# FLEX_OUTPUT.net
KiCad netlist of a schematic drawn in Altium Designer
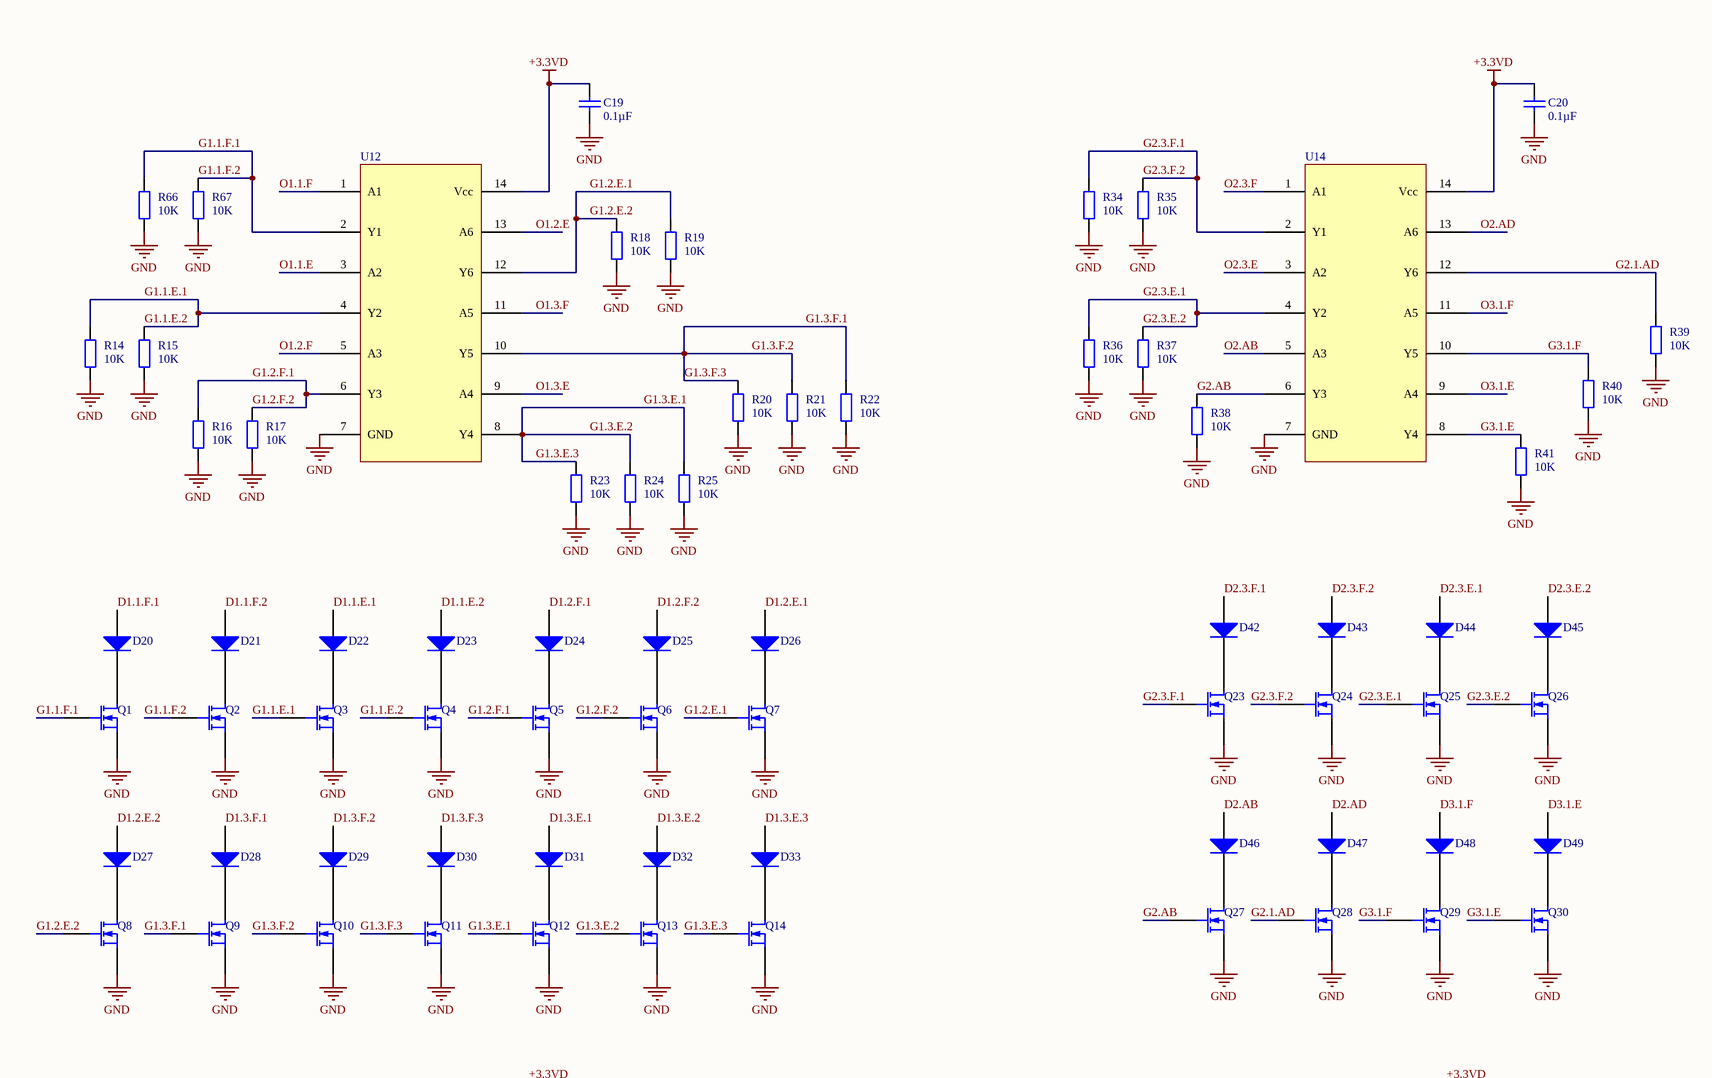
[diagram p0: FLEX_OUTPUT.SchDoc, top left]
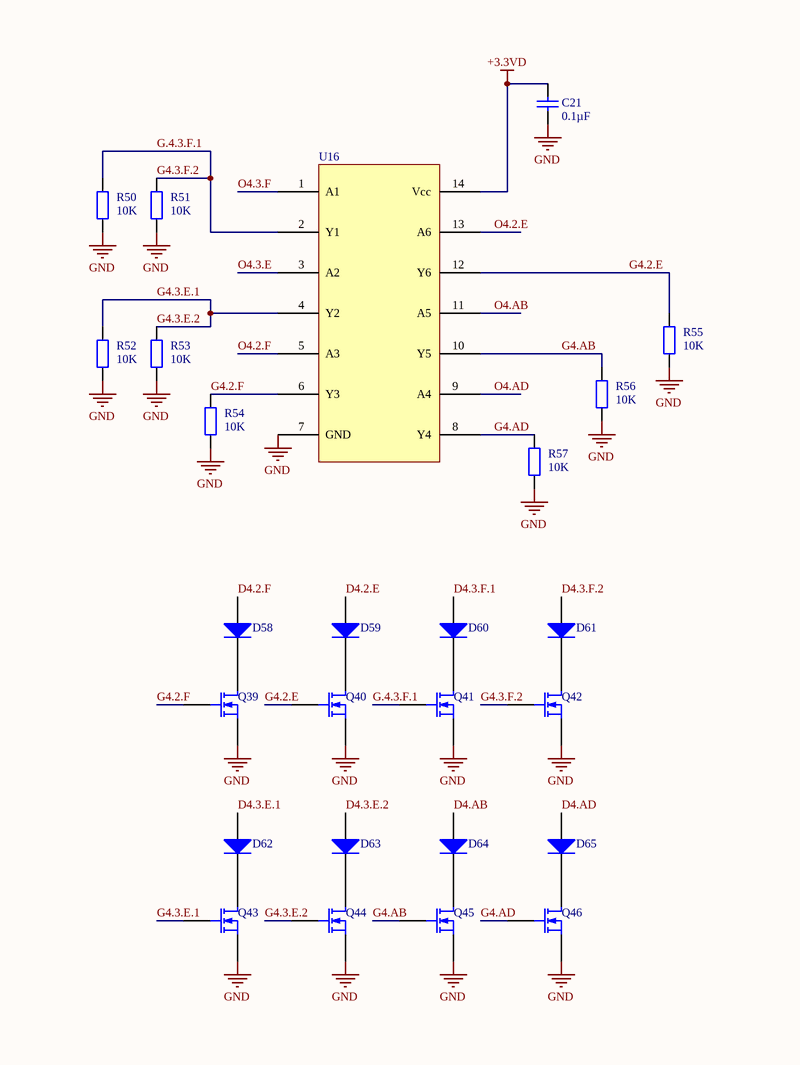
[diagram p1: FLEX_OUTPUT.SchDoc, top right]
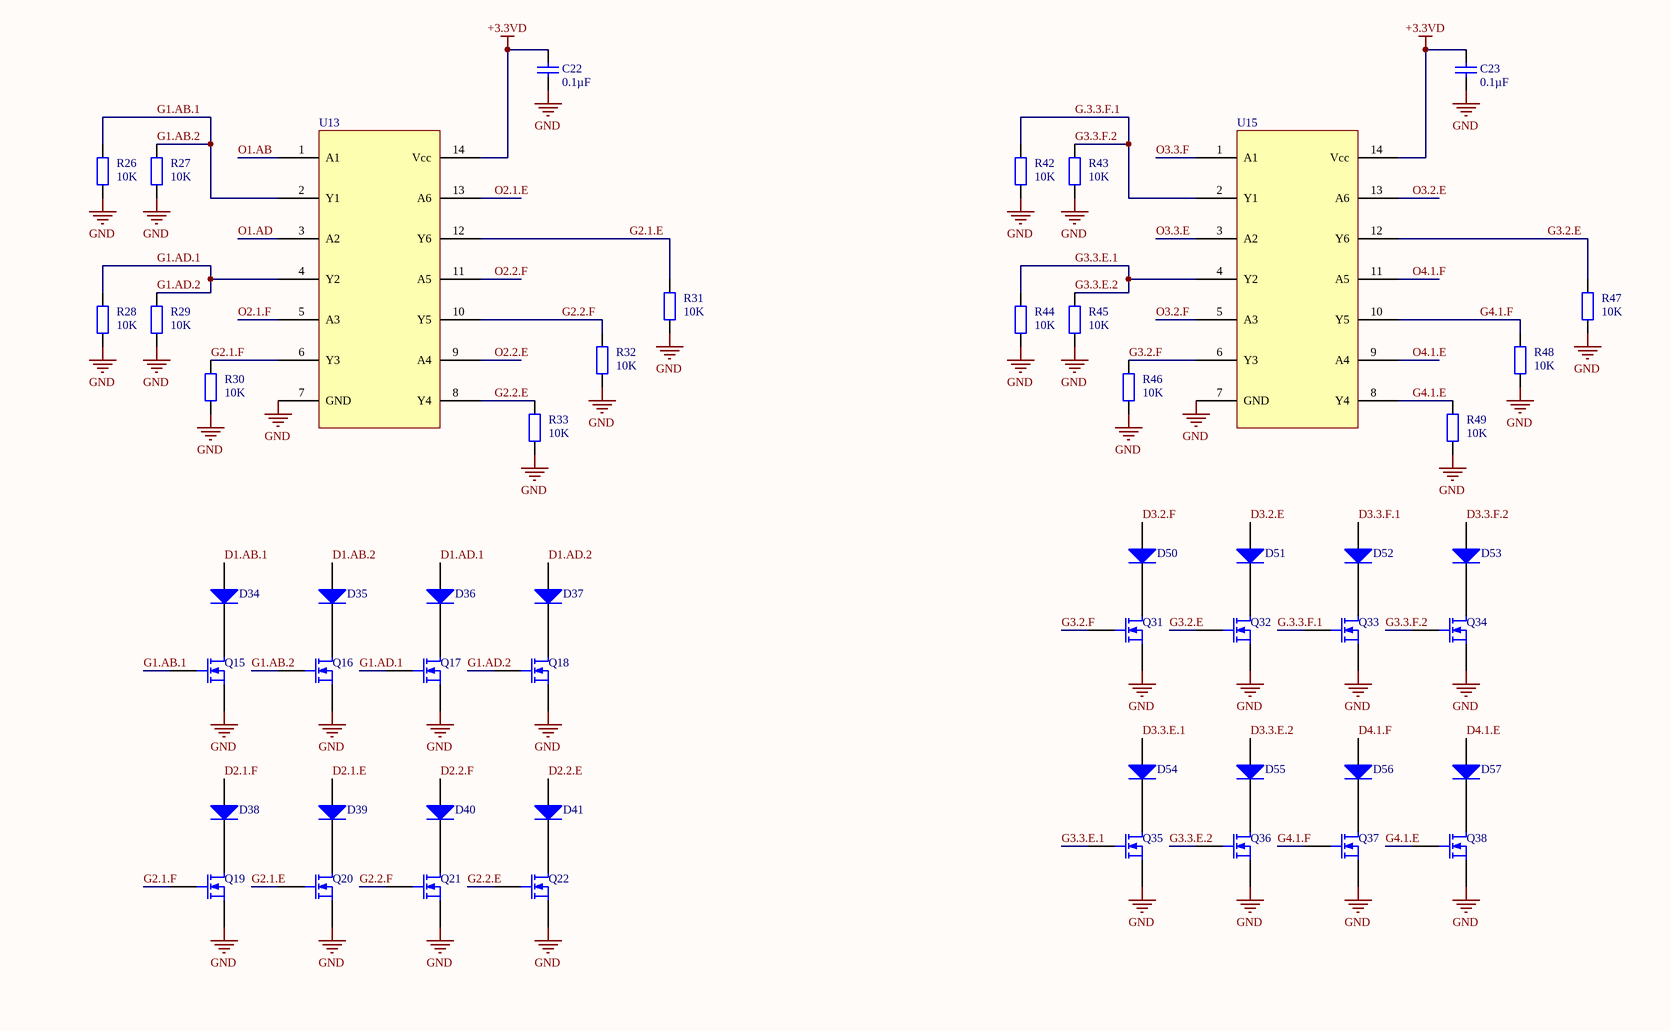
[diagram p2: FLEX_OUTPUT.SchDoc, bottom left]
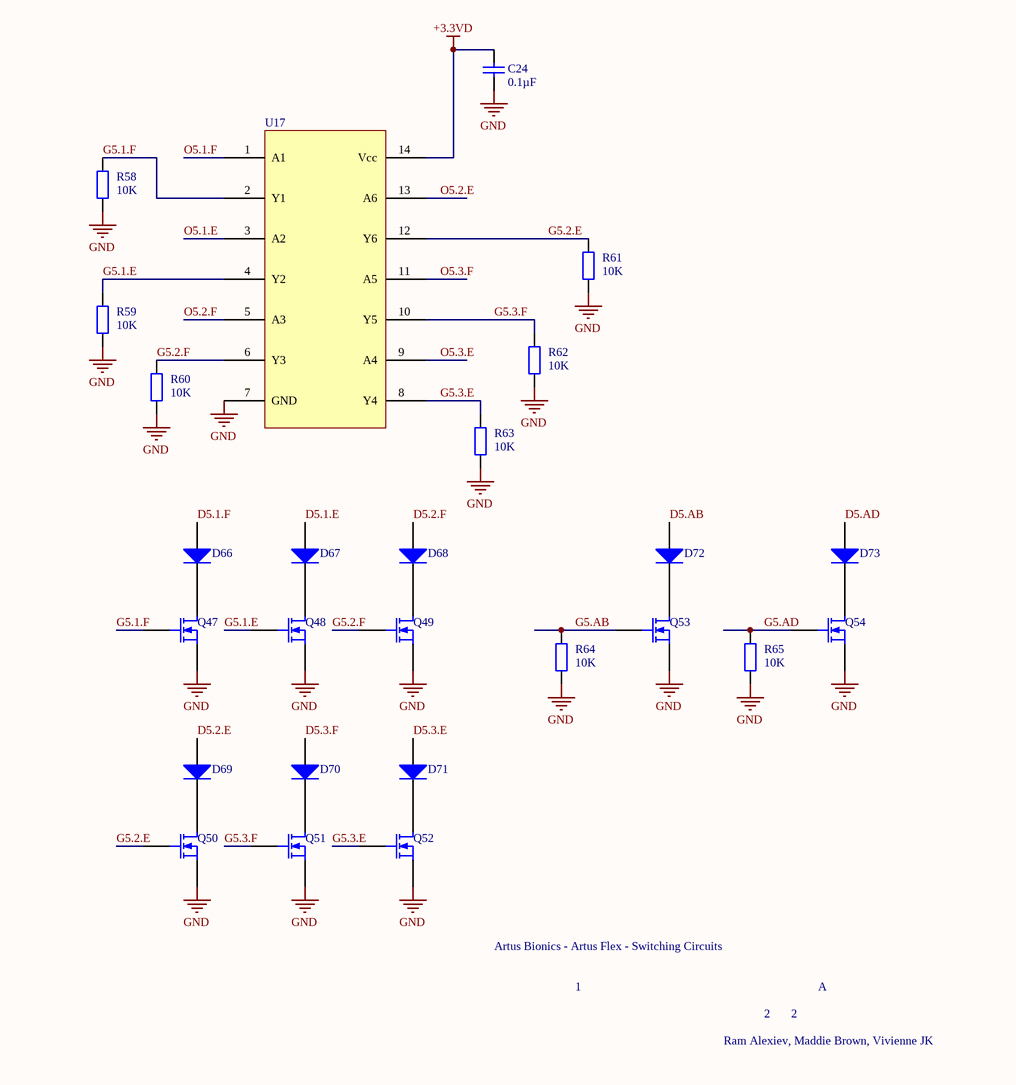
[diagram p3: FLEX_OUTPUT.SchDoc, bottom right]

(export (version "E")
  (design (tool "Eeschema 10.0.6"))
  (components
    (comp (ref "C19")
      (value "0.1µF")
      (footprint "TDK C-Series (1608)")
      (description "Capacitor")
      (fields (field (name "Comment") "Cap") (field (name "PUBLISHER") "Altium Limited"))
      (libsource (lib "Miscellaneous Devices") (part "Cap"))
    )
    (comp (ref "C20")
      (value "0.1µF")
      (footprint "TDK C-Series (1608)")
      (description "Capacitor")
      (fields (field (name "Comment") "Cap") (field (name "PUBLISHER") "Altium Limited"))
      (libsource (lib "Miscellaneous Devices") (part "Cap"))
    )
    (comp (ref "C21")
      (value "0.1µF")
      (footprint "TDK C-Series (1608)")
      (description "Capacitor")
      (fields (field (name "Comment") "Cap") (field (name "PUBLISHER") "Altium Limited"))
      (libsource (lib "Miscellaneous Devices") (part "Cap"))
    )
    (comp (ref "C22")
      (value "0.1µF")
      (footprint "TDK C-Series (1608)")
      (description "Capacitor")
      (fields (field (name "Comment") "Cap") (field (name "PUBLISHER") "Altium Limited"))
      (libsource (lib "Miscellaneous Devices") (part "Cap"))
    )
    (comp (ref "C23")
      (value "0.1µF")
      (footprint "TDK C-Series (1608)")
      (description "Capacitor")
      (fields (field (name "Comment") "Cap") (field (name "PUBLISHER") "Altium Limited"))
      (libsource (lib "Miscellaneous Devices") (part "Cap"))
    )
    (comp (ref "C24")
      (value "0.1µF")
      (footprint "TDK C-Series (1608)")
      (description "Capacitor")
      (fields (field (name "Comment") "Cap") (field (name "PUBLISHER") "Altium Limited"))
      (libsource (lib "Miscellaneous Devices") (part "Cap"))
    )
    (comp (ref "D20")
      (value "de")
      (footprint "Diode_Shottky")
      (description "Default Diode")
      (fields (field (name "PUBLISHER") "Altium Limited"))
      (libsource (lib "Miscellaneous Devices") (part "Diode"))
    )
    (comp (ref "D21")
      (value "de")
      (footprint "Diode_Shottky")
      (description "Default Diode")
      (fields (field (name "PUBLISHER") "Altium Limited"))
      (libsource (lib "Miscellaneous Devices") (part "Diode"))
    )
    (comp (ref "D22")
      (value "de")
      (footprint "Diode_Shottky")
      (description "Default Diode")
      (fields (field (name "PUBLISHER") "Altium Limited"))
      (libsource (lib "Miscellaneous Devices") (part "Diode"))
    )
    (comp (ref "D23")
      (value "de")
      (footprint "Diode_Shottky")
      (description "Default Diode")
      (fields (field (name "PUBLISHER") "Altium Limited"))
      (libsource (lib "Miscellaneous Devices") (part "Diode"))
    )
    (comp (ref "D24")
      (value "de")
      (footprint "Diode_Shottky")
      (description "Default Diode")
      (fields (field (name "PUBLISHER") "Altium Limited"))
      (libsource (lib "Miscellaneous Devices") (part "Diode"))
    )
    (comp (ref "D25")
      (value "de")
      (footprint "Diode_Shottky")
      (description "Default Diode")
      (fields (field (name "PUBLISHER") "Altium Limited"))
      (libsource (lib "Miscellaneous Devices") (part "Diode"))
    )
    (comp (ref "D26")
      (value "de")
      (footprint "Diode_Shottky")
      (description "Default Diode")
      (fields (field (name "PUBLISHER") "Altium Limited"))
      (libsource (lib "Miscellaneous Devices") (part "Diode"))
    )
    (comp (ref "D27")
      (value "de")
      (footprint "Diode_Shottky")
      (description "Default Diode")
      (fields (field (name "PUBLISHER") "Altium Limited"))
      (libsource (lib "Miscellaneous Devices") (part "Diode"))
    )
    (comp (ref "D28")
      (value "de")
      (footprint "Diode_Shottky")
      (description "Default Diode")
      (fields (field (name "PUBLISHER") "Altium Limited"))
      (libsource (lib "Miscellaneous Devices") (part "Diode"))
    )
    (comp (ref "D29")
      (value "de")
      (footprint "Diode_Shottky")
      (description "Default Diode")
      (fields (field (name "PUBLISHER") "Altium Limited"))
      (libsource (lib "Miscellaneous Devices") (part "Diode"))
    )
    (comp (ref "D30")
      (value "de")
      (footprint "Diode_Shottky")
      (description "Default Diode")
      (fields (field (name "PUBLISHER") "Altium Limited"))
      (libsource (lib "Miscellaneous Devices") (part "Diode"))
    )
    (comp (ref "D31")
      (value "de")
      (footprint "Diode_Shottky")
      (description "Default Diode")
      (fields (field (name "PUBLISHER") "Altium Limited"))
      (libsource (lib "Miscellaneous Devices") (part "Diode"))
    )
    (comp (ref "D32")
      (value "de")
      (footprint "Diode_Shottky")
      (description "Default Diode")
      (fields (field (name "PUBLISHER") "Altium Limited"))
      (libsource (lib "Miscellaneous Devices") (part "Diode"))
    )
    (comp (ref "D33")
      (value "de")
      (footprint "Diode_Shottky")
      (description "Default Diode")
      (fields (field (name "PUBLISHER") "Altium Limited"))
      (libsource (lib "Miscellaneous Devices") (part "Diode"))
    )
    (comp (ref "D34")
      (value "de")
      (footprint "Diode_Shottky")
      (description "Default Diode")
      (fields (field (name "PUBLISHER") "Altium Limited"))
      (libsource (lib "Miscellaneous Devices") (part "Diode"))
    )
    (comp (ref "D35")
      (value "de")
      (footprint "Diode_Shottky")
      (description "Default Diode")
      (fields (field (name "PUBLISHER") "Altium Limited"))
      (libsource (lib "Miscellaneous Devices") (part "Diode"))
    )
    (comp (ref "D36")
      (value "de")
      (footprint "Diode_Shottky")
      (description "Default Diode")
      (fields (field (name "PUBLISHER") "Altium Limited"))
      (libsource (lib "Miscellaneous Devices") (part "Diode"))
    )
    (comp (ref "D37")
      (value "de")
      (footprint "Diode_Shottky")
      (description "Default Diode")
      (fields (field (name "PUBLISHER") "Altium Limited"))
      (libsource (lib "Miscellaneous Devices") (part "Diode"))
    )
    (comp (ref "D38")
      (value "de")
      (footprint "Diode_Shottky")
      (description "Default Diode")
      (fields (field (name "PUBLISHER") "Altium Limited"))
      (libsource (lib "Miscellaneous Devices") (part "Diode"))
    )
    (comp (ref "D39")
      (value "de")
      (footprint "Diode_Shottky")
      (description "Default Diode")
      (fields (field (name "PUBLISHER") "Altium Limited"))
      (libsource (lib "Miscellaneous Devices") (part "Diode"))
    )
    (comp (ref "D40")
      (value "de")
      (footprint "Diode_Shottky")
      (description "Default Diode")
      (fields (field (name "PUBLISHER") "Altium Limited"))
      (libsource (lib "Miscellaneous Devices") (part "Diode"))
    )
    (comp (ref "D41")
      (value "de")
      (footprint "Diode_Shottky")
      (description "Default Diode")
      (fields (field (name "PUBLISHER") "Altium Limited"))
      (libsource (lib "Miscellaneous Devices") (part "Diode"))
    )
    (comp (ref "D42")
      (value "de")
      (footprint "Diode_Shottky")
      (description "Default Diode")
      (fields (field (name "PUBLISHER") "Altium Limited"))
      (libsource (lib "Miscellaneous Devices") (part "Diode"))
    )
    (comp (ref "D43")
      (value "de")
      (footprint "Diode_Shottky")
      (description "Default Diode")
      (fields (field (name "PUBLISHER") "Altium Limited"))
      (libsource (lib "Miscellaneous Devices") (part "Diode"))
    )
    (comp (ref "D44")
      (value "de")
      (footprint "Diode_Shottky")
      (description "Default Diode")
      (fields (field (name "PUBLISHER") "Altium Limited"))
      (libsource (lib "Miscellaneous Devices") (part "Diode"))
    )
    (comp (ref "D45")
      (value "de")
      (footprint "Diode_Shottky")
      (description "Default Diode")
      (fields (field (name "PUBLISHER") "Altium Limited"))
      (libsource (lib "Miscellaneous Devices") (part "Diode"))
    )
    (comp (ref "D46")
      (value "de")
      (footprint "Diode_Shottky")
      (description "Default Diode")
      (fields (field (name "PUBLISHER") "Altium Limited"))
      (libsource (lib "Miscellaneous Devices") (part "Diode"))
    )
    (comp (ref "D47")
      (value "de")
      (footprint "Diode_Shottky")
      (description "Default Diode")
      (fields (field (name "PUBLISHER") "Altium Limited"))
      (libsource (lib "Miscellaneous Devices") (part "Diode"))
    )
    (comp (ref "D48")
      (value "de")
      (footprint "Diode_Shottky")
      (description "Default Diode")
      (fields (field (name "PUBLISHER") "Altium Limited"))
      (libsource (lib "Miscellaneous Devices") (part "Diode"))
    )
    (comp (ref "D49")
      (value "de")
      (footprint "Diode_Shottky")
      (description "Default Diode")
      (fields (field (name "PUBLISHER") "Altium Limited"))
      (libsource (lib "Miscellaneous Devices") (part "Diode"))
    )
    (comp (ref "D50")
      (value "de")
      (footprint "Diode_Shottky")
      (description "Default Diode")
      (fields (field (name "PUBLISHER") "Altium Limited"))
      (libsource (lib "Miscellaneous Devices") (part "Diode"))
    )
    (comp (ref "D51")
      (value "de")
      (footprint "Diode_Shottky")
      (description "Default Diode")
      (fields (field (name "PUBLISHER") "Altium Limited"))
      (libsource (lib "Miscellaneous Devices") (part "Diode"))
    )
    (comp (ref "D52")
      (value "de")
      (footprint "Diode_Shottky")
      (description "Default Diode")
      (fields (field (name "PUBLISHER") "Altium Limited"))
      (libsource (lib "Miscellaneous Devices") (part "Diode"))
    )
    (comp (ref "D53")
      (value "de")
      (footprint "Diode_Shottky")
      (description "Default Diode")
      (fields (field (name "PUBLISHER") "Altium Limited"))
      (libsource (lib "Miscellaneous Devices") (part "Diode"))
    )
    (comp (ref "D54")
      (value "de")
      (footprint "Diode_Shottky")
      (description "Default Diode")
      (fields (field (name "PUBLISHER") "Altium Limited"))
      (libsource (lib "Miscellaneous Devices") (part "Diode"))
    )
    (comp (ref "D55")
      (value "de")
      (footprint "Diode_Shottky")
      (description "Default Diode")
      (fields (field (name "PUBLISHER") "Altium Limited"))
      (libsource (lib "Miscellaneous Devices") (part "Diode"))
    )
    (comp (ref "D56")
      (value "de")
      (footprint "Diode_Shottky")
      (description "Default Diode")
      (fields (field (name "PUBLISHER") "Altium Limited"))
      (libsource (lib "Miscellaneous Devices") (part "Diode"))
    )
    (comp (ref "D57")
      (value "de")
      (footprint "Diode_Shottky")
      (description "Default Diode")
      (fields (field (name "PUBLISHER") "Altium Limited"))
      (libsource (lib "Miscellaneous Devices") (part "Diode"))
    )
    (comp (ref "D58")
      (value "de")
      (footprint "Diode_Shottky")
      (description "Default Diode")
      (fields (field (name "PUBLISHER") "Altium Limited"))
      (libsource (lib "Miscellaneous Devices") (part "Diode"))
    )
    (comp (ref "D59")
      (value "de")
      (footprint "Diode_Shottky")
      (description "Default Diode")
      (fields (field (name "PUBLISHER") "Altium Limited"))
      (libsource (lib "Miscellaneous Devices") (part "Diode"))
    )
    (comp (ref "D60")
      (value "de")
      (footprint "Diode_Shottky")
      (description "Default Diode")
      (fields (field (name "PUBLISHER") "Altium Limited"))
      (libsource (lib "Miscellaneous Devices") (part "Diode"))
    )
    (comp (ref "D61")
      (value "de")
      (footprint "Diode_Shottky")
      (description "Default Diode")
      (fields (field (name "PUBLISHER") "Altium Limited"))
      (libsource (lib "Miscellaneous Devices") (part "Diode"))
    )
    (comp (ref "D62")
      (value "de")
      (footprint "Diode_Shottky")
      (description "Default Diode")
      (fields (field (name "PUBLISHER") "Altium Limited"))
      (libsource (lib "Miscellaneous Devices") (part "Diode"))
    )
    (comp (ref "D63")
      (value "de")
      (footprint "Diode_Shottky")
      (description "Default Diode")
      (fields (field (name "PUBLISHER") "Altium Limited"))
      (libsource (lib "Miscellaneous Devices") (part "Diode"))
    )
    (comp (ref "D64")
      (value "de")
      (footprint "Diode_Shottky")
      (description "Default Diode")
      (fields (field (name "PUBLISHER") "Altium Limited"))
      (libsource (lib "Miscellaneous Devices") (part "Diode"))
    )
    (comp (ref "D65")
      (value "de")
      (footprint "Diode_Shottky")
      (description "Default Diode")
      (fields (field (name "PUBLISHER") "Altium Limited"))
      (libsource (lib "Miscellaneous Devices") (part "Diode"))
    )
    (comp (ref "D66")
      (value "de")
      (footprint "Diode_Shottky")
      (description "Default Diode")
      (fields (field (name "PUBLISHER") "Altium Limited"))
      (libsource (lib "Miscellaneous Devices") (part "Diode"))
    )
    (comp (ref "D67")
      (value "de")
      (footprint "Diode_Shottky")
      (description "Default Diode")
      (fields (field (name "PUBLISHER") "Altium Limited"))
      (libsource (lib "Miscellaneous Devices") (part "Diode"))
    )
    (comp (ref "D68")
      (value "de")
      (footprint "Diode_Shottky")
      (description "Default Diode")
      (fields (field (name "PUBLISHER") "Altium Limited"))
      (libsource (lib "Miscellaneous Devices") (part "Diode"))
    )
    (comp (ref "D69")
      (value "de")
      (footprint "Diode_Shottky")
      (description "Default Diode")
      (fields (field (name "PUBLISHER") "Altium Limited"))
      (libsource (lib "Miscellaneous Devices") (part "Diode"))
    )
    (comp (ref "D70")
      (value "de")
      (footprint "Diode_Shottky")
      (description "Default Diode")
      (fields (field (name "PUBLISHER") "Altium Limited"))
      (libsource (lib "Miscellaneous Devices") (part "Diode"))
    )
    (comp (ref "D71")
      (value "de")
      (footprint "Diode_Shottky")
      (description "Default Diode")
      (fields (field (name "PUBLISHER") "Altium Limited"))
      (libsource (lib "Miscellaneous Devices") (part "Diode"))
    )
    (comp (ref "D72")
      (value "de")
      (footprint "Diode_Shottky")
      (description "Default Diode")
      (fields (field (name "PUBLISHER") "Altium Limited"))
      (libsource (lib "Miscellaneous Devices") (part "Diode"))
    )
    (comp (ref "D73")
      (value "de")
      (footprint "Diode_Shottky")
      (description "Default Diode")
      (fields (field (name "PUBLISHER") "Altium Limited"))
      (libsource (lib "Miscellaneous Devices") (part "Diode"))
    )
    (comp (ref "Q1")
      (value "~")
      (footprint "MOSFET SOT90P236X110-3N")
      (description "N-Channel MOSFET")
      (fields (field (name "PUBLISHER") "Altium Limited"))
      (libsource (lib "Miscellaneous Devices") (part "MOSFET-N"))
    )
    (comp (ref "Q2")
      (value "~")
      (footprint "MOSFET SOT90P236X110-3N")
      (description "N-Channel MOSFET")
      (fields (field (name "PUBLISHER") "Altium Limited"))
      (libsource (lib "Miscellaneous Devices") (part "MOSFET-N"))
    )
    (comp (ref "Q3")
      (value "~")
      (footprint "MOSFET SOT90P236X110-3N")
      (description "N-Channel MOSFET")
      (fields (field (name "PUBLISHER") "Altium Limited"))
      (libsource (lib "Miscellaneous Devices") (part "MOSFET-N"))
    )
    (comp (ref "Q4")
      (value "~")
      (footprint "MOSFET SOT90P236X110-3N")
      (description "N-Channel MOSFET")
      (fields (field (name "PUBLISHER") "Altium Limited"))
      (libsource (lib "Miscellaneous Devices") (part "MOSFET-N"))
    )
    (comp (ref "Q5")
      (value "~")
      (footprint "MOSFET SOT90P236X110-3N")
      (description "N-Channel MOSFET")
      (fields (field (name "PUBLISHER") "Altium Limited"))
      (libsource (lib "Miscellaneous Devices") (part "MOSFET-N"))
    )
    (comp (ref "Q6")
      (value "~")
      (footprint "MOSFET SOT90P236X110-3N")
      (description "N-Channel MOSFET")
      (fields (field (name "PUBLISHER") "Altium Limited"))
      (libsource (lib "Miscellaneous Devices") (part "MOSFET-N"))
    )
    (comp (ref "Q7")
      (value "~")
      (footprint "MOSFET SOT90P236X110-3N")
      (description "N-Channel MOSFET")
      (fields (field (name "PUBLISHER") "Altium Limited"))
      (libsource (lib "Miscellaneous Devices") (part "MOSFET-N"))
    )
    (comp (ref "Q8")
      (value "~")
      (footprint "MOSFET SOT90P236X110-3N")
      (description "N-Channel MOSFET")
      (fields (field (name "PUBLISHER") "Altium Limited"))
      (libsource (lib "Miscellaneous Devices") (part "MOSFET-N"))
    )
    (comp (ref "Q9")
      (value "~")
      (footprint "MOSFET SOT90P236X110-3N")
      (description "N-Channel MOSFET")
      (fields (field (name "PUBLISHER") "Altium Limited"))
      (libsource (lib "Miscellaneous Devices") (part "MOSFET-N"))
    )
    (comp (ref "Q10")
      (value "~")
      (footprint "MOSFET SOT90P236X110-3N")
      (description "N-Channel MOSFET")
      (fields (field (name "PUBLISHER") "Altium Limited"))
      (libsource (lib "Miscellaneous Devices") (part "MOSFET-N"))
    )
    (comp (ref "Q11")
      (value "~")
      (footprint "MOSFET SOT90P236X110-3N")
      (description "N-Channel MOSFET")
      (fields (field (name "PUBLISHER") "Altium Limited"))
      (libsource (lib "Miscellaneous Devices") (part "MOSFET-N"))
    )
    (comp (ref "Q12")
      (value "~")
      (footprint "MOSFET SOT90P236X110-3N")
      (description "N-Channel MOSFET")
      (fields (field (name "PUBLISHER") "Altium Limited"))
      (libsource (lib "Miscellaneous Devices") (part "MOSFET-N"))
    )
    (comp (ref "Q13")
      (value "~")
      (footprint "MOSFET SOT90P236X110-3N")
      (description "N-Channel MOSFET")
      (fields (field (name "PUBLISHER") "Altium Limited"))
      (libsource (lib "Miscellaneous Devices") (part "MOSFET-N"))
    )
    (comp (ref "Q14")
      (value "~")
      (footprint "MOSFET SOT90P236X110-3N")
      (description "N-Channel MOSFET")
      (fields (field (name "PUBLISHER") "Altium Limited"))
      (libsource (lib "Miscellaneous Devices") (part "MOSFET-N"))
    )
    (comp (ref "Q15")
      (value "~")
      (footprint "MOSFET SOT90P236X110-3N")
      (description "N-Channel MOSFET")
      (fields (field (name "PUBLISHER") "Altium Limited"))
      (libsource (lib "Miscellaneous Devices") (part "MOSFET-N"))
    )
    (comp (ref "Q16")
      (value "~")
      (footprint "MOSFET SOT90P236X110-3N")
      (description "N-Channel MOSFET")
      (fields (field (name "PUBLISHER") "Altium Limited"))
      (libsource (lib "Miscellaneous Devices") (part "MOSFET-N"))
    )
    (comp (ref "Q17")
      (value "~")
      (footprint "MOSFET SOT90P236X110-3N")
      (description "N-Channel MOSFET")
      (fields (field (name "PUBLISHER") "Altium Limited"))
      (libsource (lib "Miscellaneous Devices") (part "MOSFET-N"))
    )
    (comp (ref "Q18")
      (value "~")
      (footprint "MOSFET SOT90P236X110-3N")
      (description "N-Channel MOSFET")
      (fields (field (name "PUBLISHER") "Altium Limited"))
      (libsource (lib "Miscellaneous Devices") (part "MOSFET-N"))
    )
    (comp (ref "Q19")
      (value "~")
      (footprint "MOSFET SOT90P236X110-3N")
      (description "N-Channel MOSFET")
      (fields (field (name "PUBLISHER") "Altium Limited"))
      (libsource (lib "Miscellaneous Devices") (part "MOSFET-N"))
    )
    (comp (ref "Q20")
      (value "~")
      (footprint "MOSFET SOT90P236X110-3N")
      (description "N-Channel MOSFET")
      (fields (field (name "PUBLISHER") "Altium Limited"))
      (libsource (lib "Miscellaneous Devices") (part "MOSFET-N"))
    )
    (comp (ref "Q21")
      (value "~")
      (footprint "MOSFET SOT90P236X110-3N")
      (description "N-Channel MOSFET")
      (fields (field (name "PUBLISHER") "Altium Limited"))
      (libsource (lib "Miscellaneous Devices") (part "MOSFET-N"))
    )
    (comp (ref "Q22")
      (value "~")
      (footprint "MOSFET SOT90P236X110-3N")
      (description "N-Channel MOSFET")
      (fields (field (name "PUBLISHER") "Altium Limited"))
      (libsource (lib "Miscellaneous Devices") (part "MOSFET-N"))
    )
    (comp (ref "Q23")
      (value "~")
      (footprint "MOSFET SOT90P236X110-3N")
      (description "N-Channel MOSFET")
      (fields (field (name "PUBLISHER") "Altium Limited"))
      (libsource (lib "Miscellaneous Devices") (part "MOSFET-N"))
    )
    (comp (ref "Q24")
      (value "~")
      (footprint "MOSFET SOT90P236X110-3N")
      (description "N-Channel MOSFET")
      (fields (field (name "PUBLISHER") "Altium Limited"))
      (libsource (lib "Miscellaneous Devices") (part "MOSFET-N"))
    )
    (comp (ref "Q25")
      (value "~")
      (footprint "MOSFET SOT90P236X110-3N")
      (description "N-Channel MOSFET")
      (fields (field (name "PUBLISHER") "Altium Limited"))
      (libsource (lib "Miscellaneous Devices") (part "MOSFET-N"))
    )
    (comp (ref "Q26")
      (value "~")
      (footprint "MOSFET SOT90P236X110-3N")
      (description "N-Channel MOSFET")
      (fields (field (name "PUBLISHER") "Altium Limited"))
      (libsource (lib "Miscellaneous Devices") (part "MOSFET-N"))
    )
    (comp (ref "Q27")
      (value "~")
      (footprint "MOSFET SOT90P236X110-3N")
      (description "N-Channel MOSFET")
      (fields (field (name "PUBLISHER") "Altium Limited"))
      (libsource (lib "Miscellaneous Devices") (part "MOSFET-N"))
    )
    (comp (ref "Q28")
      (value "~")
      (footprint "MOSFET SOT90P236X110-3N")
      (description "N-Channel MOSFET")
      (fields (field (name "PUBLISHER") "Altium Limited"))
      (libsource (lib "Miscellaneous Devices") (part "MOSFET-N"))
    )
    (comp (ref "Q29")
      (value "~")
      (footprint "MOSFET SOT90P236X110-3N")
      (description "N-Channel MOSFET")
      (fields (field (name "PUBLISHER") "Altium Limited"))
      (libsource (lib "Miscellaneous Devices") (part "MOSFET-N"))
    )
    (comp (ref "Q30")
      (value "~")
      (footprint "MOSFET SOT90P236X110-3N")
      (description "N-Channel MOSFET")
      (fields (field (name "PUBLISHER") "Altium Limited"))
      (libsource (lib "Miscellaneous Devices") (part "MOSFET-N"))
    )
    (comp (ref "Q31")
      (value "~")
      (footprint "MOSFET SOT90P236X110-3N")
      (description "N-Channel MOSFET")
      (fields (field (name "PUBLISHER") "Altium Limited"))
      (libsource (lib "Miscellaneous Devices") (part "MOSFET-N"))
    )
    (comp (ref "Q32")
      (value "~")
      (footprint "MOSFET SOT90P236X110-3N")
      (description "N-Channel MOSFET")
      (fields (field (name "PUBLISHER") "Altium Limited"))
      (libsource (lib "Miscellaneous Devices") (part "MOSFET-N"))
    )
    (comp (ref "Q33")
      (value "~")
      (footprint "MOSFET SOT90P236X110-3N")
      (description "N-Channel MOSFET")
      (fields (field (name "PUBLISHER") "Altium Limited"))
      (libsource (lib "Miscellaneous Devices") (part "MOSFET-N"))
    )
    (comp (ref "Q34")
      (value "~")
      (footprint "MOSFET SOT90P236X110-3N")
      (description "N-Channel MOSFET")
      (fields (field (name "PUBLISHER") "Altium Limited"))
      (libsource (lib "Miscellaneous Devices") (part "MOSFET-N"))
    )
    (comp (ref "Q35")
      (value "~")
      (footprint "MOSFET SOT90P236X110-3N")
      (description "N-Channel MOSFET")
      (fields (field (name "PUBLISHER") "Altium Limited"))
      (libsource (lib "Miscellaneous Devices") (part "MOSFET-N"))
    )
    (comp (ref "Q36")
      (value "~")
      (footprint "MOSFET SOT90P236X110-3N")
      (description "N-Channel MOSFET")
      (fields (field (name "PUBLISHER") "Altium Limited"))
      (libsource (lib "Miscellaneous Devices") (part "MOSFET-N"))
    )
    (comp (ref "Q37")
      (value "~")
      (footprint "MOSFET SOT90P236X110-3N")
      (description "N-Channel MOSFET")
      (fields (field (name "PUBLISHER") "Altium Limited"))
      (libsource (lib "Miscellaneous Devices") (part "MOSFET-N"))
    )
    (comp (ref "Q38")
      (value "~")
      (footprint "MOSFET SOT90P236X110-3N")
      (description "N-Channel MOSFET")
      (fields (field (name "PUBLISHER") "Altium Limited"))
      (libsource (lib "Miscellaneous Devices") (part "MOSFET-N"))
    )
    (comp (ref "Q39")
      (value "~")
      (footprint "MOSFET SOT90P236X110-3N")
      (description "N-Channel MOSFET")
      (fields (field (name "PUBLISHER") "Altium Limited"))
      (libsource (lib "Miscellaneous Devices") (part "MOSFET-N"))
    )
    (comp (ref "Q40")
      (value "~")
      (footprint "MOSFET SOT90P236X110-3N")
      (description "N-Channel MOSFET")
      (fields (field (name "PUBLISHER") "Altium Limited"))
      (libsource (lib "Miscellaneous Devices") (part "MOSFET-N"))
    )
    (comp (ref "Q41")
      (value "~")
      (footprint "MOSFET SOT90P236X110-3N")
      (description "N-Channel MOSFET")
      (fields (field (name "PUBLISHER") "Altium Limited"))
      (libsource (lib "Miscellaneous Devices") (part "MOSFET-N"))
    )
    (comp (ref "Q42")
      (value "~")
      (footprint "MOSFET SOT90P236X110-3N")
      (description "N-Channel MOSFET")
      (fields (field (name "PUBLISHER") "Altium Limited"))
      (libsource (lib "Miscellaneous Devices") (part "MOSFET-N"))
    )
    (comp (ref "Q43")
      (value "~")
      (footprint "MOSFET SOT90P236X110-3N")
      (description "N-Channel MOSFET")
      (fields (field (name "PUBLISHER") "Altium Limited"))
      (libsource (lib "Miscellaneous Devices") (part "MOSFET-N"))
    )
    (comp (ref "Q44")
      (value "~")
      (footprint "MOSFET SOT90P236X110-3N")
      (description "N-Channel MOSFET")
      (fields (field (name "PUBLISHER") "Altium Limited"))
      (libsource (lib "Miscellaneous Devices") (part "MOSFET-N"))
    )
    (comp (ref "Q45")
      (value "~")
      (footprint "MOSFET SOT90P236X110-3N")
      (description "N-Channel MOSFET")
      (fields (field (name "PUBLISHER") "Altium Limited"))
      (libsource (lib "Miscellaneous Devices") (part "MOSFET-N"))
    )
    (comp (ref "Q46")
      (value "~")
      (footprint "MOSFET SOT90P236X110-3N")
      (description "N-Channel MOSFET")
      (fields (field (name "PUBLISHER") "Altium Limited"))
      (libsource (lib "Miscellaneous Devices") (part "MOSFET-N"))
    )
    (comp (ref "Q47")
      (value "~")
      (footprint "MOSFET SOT90P236X110-3N")
      (description "N-Channel MOSFET")
      (fields (field (name "PUBLISHER") "Altium Limited"))
      (libsource (lib "Miscellaneous Devices") (part "MOSFET-N"))
    )
    (comp (ref "Q48")
      (value "~")
      (footprint "MOSFET SOT90P236X110-3N")
      (description "N-Channel MOSFET")
      (fields (field (name "PUBLISHER") "Altium Limited"))
      (libsource (lib "Miscellaneous Devices") (part "MOSFET-N"))
    )
    (comp (ref "Q49")
      (value "~")
      (footprint "MOSFET SOT90P236X110-3N")
      (description "N-Channel MOSFET")
      (fields (field (name "PUBLISHER") "Altium Limited"))
      (libsource (lib "Miscellaneous Devices") (part "MOSFET-N"))
    )
    (comp (ref "Q50")
      (value "~")
      (footprint "MOSFET SOT90P236X110-3N")
      (description "N-Channel MOSFET")
      (fields (field (name "PUBLISHER") "Altium Limited"))
      (libsource (lib "Miscellaneous Devices") (part "MOSFET-N"))
    )
    (comp (ref "Q51")
      (value "~")
      (footprint "MOSFET SOT90P236X110-3N")
      (description "N-Channel MOSFET")
      (fields (field (name "PUBLISHER") "Altium Limited"))
      (libsource (lib "Miscellaneous Devices") (part "MOSFET-N"))
    )
    (comp (ref "Q52")
      (value "~")
      (footprint "MOSFET SOT90P236X110-3N")
      (description "N-Channel MOSFET")
      (fields (field (name "PUBLISHER") "Altium Limited"))
      (libsource (lib "Miscellaneous Devices") (part "MOSFET-N"))
    )
    (comp (ref "Q53")
      (value "~")
      (footprint "MOSFET SOT90P236X110-3N")
      (description "N-Channel MOSFET")
      (fields (field (name "PUBLISHER") "Altium Limited"))
      (libsource (lib "Miscellaneous Devices") (part "MOSFET-N"))
    )
    (comp (ref "Q54")
      (value "~")
      (footprint "MOSFET SOT90P236X110-3N")
      (description "N-Channel MOSFET")
      (fields (field (name "PUBLISHER") "Altium Limited"))
      (libsource (lib "Miscellaneous Devices") (part "MOSFET-N"))
    )
    (comp (ref "R14")
      (value "10K")
      (footprint "Panasonic ERJ-Series (1608)")
      (description "Resistor")
      (fields (field (name "PUBLISHER") "Altium Limited"))
      (libsource (lib "Miscellaneous Devices") (part "Res2"))
    )
    (comp (ref "R15")
      (value "10K")
      (footprint "Panasonic ERJ-Series (1608)")
      (description "Resistor")
      (fields (field (name "PUBLISHER") "Altium Limited"))
      (libsource (lib "Miscellaneous Devices") (part "Res2"))
    )
    (comp (ref "R16")
      (value "10K")
      (footprint "Panasonic ERJ-Series (1608)")
      (description "Resistor")
      (fields (field (name "PUBLISHER") "Altium Limited"))
      (libsource (lib "Miscellaneous Devices") (part "Res2"))
    )
    (comp (ref "R17")
      (value "10K")
      (footprint "Panasonic ERJ-Series (1608)")
      (description "Resistor")
      (fields (field (name "PUBLISHER") "Altium Limited"))
      (libsource (lib "Miscellaneous Devices") (part "Res2"))
    )
    (comp (ref "R18")
      (value "10K")
      (footprint "Panasonic ERJ-Series (1608)")
      (description "Resistor")
      (fields (field (name "PUBLISHER") "Altium Limited"))
      (libsource (lib "Miscellaneous Devices") (part "Res2"))
    )
    (comp (ref "R19")
      (value "10K")
      (footprint "Panasonic ERJ-Series (1608)")
      (description "Resistor")
      (fields (field (name "PUBLISHER") "Altium Limited"))
      (libsource (lib "Miscellaneous Devices") (part "Res2"))
    )
    (comp (ref "R20")
      (value "10K")
      (footprint "Panasonic ERJ-Series (1608)")
      (description "Resistor")
      (fields (field (name "PUBLISHER") "Altium Limited"))
      (libsource (lib "Miscellaneous Devices") (part "Res2"))
    )
    (comp (ref "R21")
      (value "10K")
      (footprint "Panasonic ERJ-Series (1608)")
      (description "Resistor")
      (fields (field (name "PUBLISHER") "Altium Limited"))
      (libsource (lib "Miscellaneous Devices") (part "Res2"))
    )
    (comp (ref "R22")
      (value "10K")
      (footprint "Panasonic ERJ-Series (1608)")
      (description "Resistor")
      (fields (field (name "PUBLISHER") "Altium Limited"))
      (libsource (lib "Miscellaneous Devices") (part "Res2"))
    )
    (comp (ref "R23")
      (value "10K")
      (footprint "Panasonic ERJ-Series (1608)")
      (description "Resistor")
      (fields (field (name "PUBLISHER") "Altium Limited"))
      (libsource (lib "Miscellaneous Devices") (part "Res2"))
    )
    (comp (ref "R24")
      (value "10K")
      (footprint "Panasonic ERJ-Series (1608)")
      (description "Resistor")
      (fields (field (name "PUBLISHER") "Altium Limited"))
      (libsource (lib "Miscellaneous Devices") (part "Res2"))
    )
    (comp (ref "R25")
      (value "10K")
      (footprint "Panasonic ERJ-Series (1608)")
      (description "Resistor")
      (fields (field (name "PUBLISHER") "Altium Limited"))
      (libsource (lib "Miscellaneous Devices") (part "Res2"))
    )
    (comp (ref "R26")
      (value "10K")
      (footprint "Panasonic ERJ-Series (1608)")
      (description "Resistor")
      (fields (field (name "PUBLISHER") "Altium Limited"))
      (libsource (lib "Miscellaneous Devices") (part "Res2"))
    )
    (comp (ref "R27")
      (value "10K")
      (footprint "Panasonic ERJ-Series (1608)")
      (description "Resistor")
      (fields (field (name "PUBLISHER") "Altium Limited"))
      (libsource (lib "Miscellaneous Devices") (part "Res2"))
    )
    (comp (ref "R28")
      (value "10K")
      (footprint "Panasonic ERJ-Series (1608)")
      (description "Resistor")
      (fields (field (name "PUBLISHER") "Altium Limited"))
      (libsource (lib "Miscellaneous Devices") (part "Res2"))
    )
    (comp (ref "R29")
      (value "10K")
      (footprint "Panasonic ERJ-Series (1608)")
      (description "Resistor")
      (fields (field (name "PUBLISHER") "Altium Limited"))
      (libsource (lib "Miscellaneous Devices") (part "Res2"))
    )
    (comp (ref "R30")
      (value "10K")
      (footprint "Panasonic ERJ-Series (1608)")
      (description "Resistor")
      (fields (field (name "PUBLISHER") "Altium Limited"))
      (libsource (lib "Miscellaneous Devices") (part "Res2"))
    )
    (comp (ref "R31")
      (value "10K")
      (footprint "Panasonic ERJ-Series (1608)")
      (description "Resistor")
      (fields (field (name "PUBLISHER") "Altium Limited"))
      (libsource (lib "Miscellaneous Devices") (part "Res2"))
    )
    (comp (ref "R32")
      (value "10K")
      (footprint "Panasonic ERJ-Series (1608)")
      (description "Resistor")
      (fields (field (name "PUBLISHER") "Altium Limited"))
      (libsource (lib "Miscellaneous Devices") (part "Res2"))
    )
    (comp (ref "R33")
      (value "10K")
      (footprint "Panasonic ERJ-Series (1608)")
      (description "Resistor")
      (fields (field (name "PUBLISHER") "Altium Limited"))
      (libsource (lib "Miscellaneous Devices") (part "Res2"))
    )
    (comp (ref "R34")
      (value "10K")
      (footprint "Panasonic ERJ-Series (1608)")
      (description "Resistor")
      (fields (field (name "PUBLISHER") "Altium Limited"))
      (libsource (lib "Miscellaneous Devices") (part "Res2"))
    )
    (comp (ref "R35")
      (value "10K")
      (footprint "Panasonic ERJ-Series (1608)")
      (description "Resistor")
      (fields (field (name "PUBLISHER") "Altium Limited"))
      (libsource (lib "Miscellaneous Devices") (part "Res2"))
    )
    (comp (ref "R36")
      (value "10K")
      (footprint "Panasonic ERJ-Series (1608)")
      (description "Resistor")
      (fields (field (name "PUBLISHER") "Altium Limited"))
      (libsource (lib "Miscellaneous Devices") (part "Res2"))
    )
    (comp (ref "R37")
      (value "10K")
      (footprint "Panasonic ERJ-Series (1608)")
      (description "Resistor")
      (fields (field (name "PUBLISHER") "Altium Limited"))
      (libsource (lib "Miscellaneous Devices") (part "Res2"))
    )
    (comp (ref "R38")
      (value "10K")
      (footprint "Panasonic ERJ-Series (1608)")
      (description "Resistor")
      (fields (field (name "PUBLISHER") "Altium Limited"))
      (libsource (lib "Miscellaneous Devices") (part "Res2"))
    )
    (comp (ref "R39")
      (value "10K")
      (footprint "Panasonic ERJ-Series (1608)")
      (description "Resistor")
      (fields (field (name "PUBLISHER") "Altium Limited"))
      (libsource (lib "Miscellaneous Devices") (part "Res2"))
    )
    (comp (ref "R40")
      (value "10K")
      (footprint "Panasonic ERJ-Series (1608)")
      (description "Resistor")
      (fields (field (name "PUBLISHER") "Altium Limited"))
      (libsource (lib "Miscellaneous Devices") (part "Res2"))
    )
    (comp (ref "R41")
      (value "10K")
      (footprint "Panasonic ERJ-Series (1608)")
      (description "Resistor")
      (fields (field (name "PUBLISHER") "Altium Limited"))
      (libsource (lib "Miscellaneous Devices") (part "Res2"))
    )
    (comp (ref "R42")
      (value "10K")
      (footprint "Panasonic ERJ-Series (1608)")
      (description "Resistor")
      (fields (field (name "PUBLISHER") "Altium Limited"))
      (libsource (lib "Miscellaneous Devices") (part "Res2"))
    )
    (comp (ref "R43")
      (value "10K")
      (footprint "Panasonic ERJ-Series (1608)")
      (description "Resistor")
      (fields (field (name "PUBLISHER") "Altium Limited"))
      (libsource (lib "Miscellaneous Devices") (part "Res2"))
    )
    (comp (ref "R44")
      (value "10K")
      (footprint "Panasonic ERJ-Series (1608)")
      (description "Resistor")
      (fields (field (name "PUBLISHER") "Altium Limited"))
      (libsource (lib "Miscellaneous Devices") (part "Res2"))
    )
    (comp (ref "R45")
      (value "10K")
      (footprint "Panasonic ERJ-Series (1608)")
      (description "Resistor")
      (fields (field (name "PUBLISHER") "Altium Limited"))
      (libsource (lib "Miscellaneous Devices") (part "Res2"))
    )
    (comp (ref "R46")
      (value "10K")
      (footprint "Panasonic ERJ-Series (1608)")
      (description "Resistor")
      (fields (field (name "PUBLISHER") "Altium Limited"))
      (libsource (lib "Miscellaneous Devices") (part "Res2"))
    )
    (comp (ref "R47")
      (value "10K")
      (footprint "Panasonic ERJ-Series (1608)")
      (description "Resistor")
      (fields (field (name "PUBLISHER") "Altium Limited"))
      (libsource (lib "Miscellaneous Devices") (part "Res2"))
    )
    (comp (ref "R48")
      (value "10K")
      (footprint "Panasonic ERJ-Series (1608)")
      (description "Resistor")
      (fields (field (name "PUBLISHER") "Altium Limited"))
      (libsource (lib "Miscellaneous Devices") (part "Res2"))
    )
    (comp (ref "R49")
      (value "10K")
      (footprint "Panasonic ERJ-Series (1608)")
      (description "Resistor")
      (fields (field (name "PUBLISHER") "Altium Limited"))
      (libsource (lib "Miscellaneous Devices") (part "Res2"))
    )
    (comp (ref "R50")
      (value "10K")
      (footprint "Panasonic ERJ-Series (1608)")
      (description "Resistor")
      (fields (field (name "PUBLISHER") "Altium Limited"))
      (libsource (lib "Miscellaneous Devices") (part "Res2"))
    )
    (comp (ref "R51")
      (value "10K")
      (footprint "Panasonic ERJ-Series (1608)")
      (description "Resistor")
      (fields (field (name "PUBLISHER") "Altium Limited"))
      (libsource (lib "Miscellaneous Devices") (part "Res2"))
    )
    (comp (ref "R52")
      (value "10K")
      (footprint "Panasonic ERJ-Series (1608)")
      (description "Resistor")
      (fields (field (name "PUBLISHER") "Altium Limited"))
      (libsource (lib "Miscellaneous Devices") (part "Res2"))
    )
    (comp (ref "R53")
      (value "10K")
      (footprint "Panasonic ERJ-Series (1608)")
      (description "Resistor")
      (fields (field (name "PUBLISHER") "Altium Limited"))
      (libsource (lib "Miscellaneous Devices") (part "Res2"))
    )
    (comp (ref "R54")
      (value "10K")
      (footprint "Panasonic ERJ-Series (1608)")
      (description "Resistor")
      (fields (field (name "PUBLISHER") "Altium Limited"))
      (libsource (lib "Miscellaneous Devices") (part "Res2"))
    )
    (comp (ref "R55")
      (value "10K")
      (footprint "Panasonic ERJ-Series (1608)")
      (description "Resistor")
      (fields (field (name "PUBLISHER") "Altium Limited"))
      (libsource (lib "Miscellaneous Devices") (part "Res2"))
    )
    (comp (ref "R56")
      (value "10K")
      (footprint "Panasonic ERJ-Series (1608)")
      (description "Resistor")
      (fields (field (name "PUBLISHER") "Altium Limited"))
      (libsource (lib "Miscellaneous Devices") (part "Res2"))
    )
    (comp (ref "R57")
      (value "10K")
      (footprint "Panasonic ERJ-Series (1608)")
      (description "Resistor")
      (fields (field (name "PUBLISHER") "Altium Limited"))
      (libsource (lib "Miscellaneous Devices") (part "Res2"))
    )
    (comp (ref "R58")
      (value "10K")
      (footprint "Panasonic ERJ-Series (1608)")
      (description "Resistor")
      (fields (field (name "PUBLISHER") "Altium Limited"))
      (libsource (lib "Miscellaneous Devices") (part "Res2"))
    )
    (comp (ref "R59")
      (value "10K")
      (footprint "Panasonic ERJ-Series (1608)")
      (description "Resistor")
      (fields (field (name "PUBLISHER") "Altium Limited"))
      (libsource (lib "Miscellaneous Devices") (part "Res2"))
    )
    (comp (ref "R60")
      (value "10K")
      (footprint "Panasonic ERJ-Series (1608)")
      (description "Resistor")
      (fields (field (name "PUBLISHER") "Altium Limited"))
      (libsource (lib "Miscellaneous Devices") (part "Res2"))
    )
    (comp (ref "R61")
      (value "10K")
      (footprint "Panasonic ERJ-Series (1608)")
      (description "Resistor")
      (fields (field (name "PUBLISHER") "Altium Limited"))
      (libsource (lib "Miscellaneous Devices") (part "Res2"))
    )
    (comp (ref "R62")
      (value "10K")
      (footprint "Panasonic ERJ-Series (1608)")
      (description "Resistor")
      (fields (field (name "PUBLISHER") "Altium Limited"))
      (libsource (lib "Miscellaneous Devices") (part "Res2"))
    )
    (comp (ref "R63")
      (value "10K")
      (footprint "Panasonic ERJ-Series (1608)")
      (description "Resistor")
      (fields (field (name "PUBLISHER") "Altium Limited"))
      (libsource (lib "Miscellaneous Devices") (part "Res2"))
    )
    (comp (ref "R64")
      (value "10K")
      (footprint "Panasonic ERJ-Series (1608)")
      (description "Resistor")
      (fields (field (name "PUBLISHER") "Altium Limited"))
      (libsource (lib "Miscellaneous Devices") (part "Res2"))
    )
    (comp (ref "R65")
      (value "10K")
      (footprint "Panasonic ERJ-Series (1608)")
      (description "Resistor")
      (fields (field (name "PUBLISHER") "Altium Limited"))
      (libsource (lib "Miscellaneous Devices") (part "Res2"))
    )
    (comp (ref "R66")
      (value "10K")
      (footprint "Panasonic ERJ-Series (1608)")
      (description "Resistor")
      (fields (field (name "PUBLISHER") "Altium Limited"))
      (libsource (lib "Miscellaneous Devices") (part "Res2"))
    )
    (comp (ref "R67")
      (value "10K")
      (footprint "Panasonic ERJ-Series (1608)")
      (description "Resistor")
      (fields (field (name "PUBLISHER") "Altium Limited"))
      (libsource (lib "Miscellaneous Devices") (part "Res2"))
    )
    (comp (ref "U12")
      (value "MC74VHCT50A")
      (description "6-Channel CMOS Buffer")
      (libsource (lib "Schematics Library") (part "MC74VHCT50A"))
    )
    (comp (ref "U13")
      (value "MC74VHCT50A")
      (description "6-Channel CMOS Buffer")
      (libsource (lib "Schematics Library") (part "MC74VHCT50A"))
    )
    (comp (ref "U14")
      (value "MC74VHCT50A")
      (description "6-Channel CMOS Buffer")
      (libsource (lib "Schematics Library") (part "MC74VHCT50A"))
    )
    (comp (ref "U15")
      (value "MC74VHCT50A")
      (description "6-Channel CMOS Buffer")
      (libsource (lib "Schematics Library") (part "MC74VHCT50A"))
    )
    (comp (ref "U16")
      (value "MC74VHCT50A")
      (description "6-Channel CMOS Buffer")
      (libsource (lib "Schematics Library") (part "MC74VHCT50A"))
    )
    (comp (ref "U17")
      (value "MC74VHCT50A")
      (description "6-Channel CMOS Buffer")
      (libsource (lib "Schematics Library") (part "MC74VHCT50A"))
    )
  )
  (nets
    (net (code "1") (name "+3.3VD") (class "Default")
      (node (ref "C19") (pin "2") (pinfunction "2_2") (pintype "passive"))
      (node (ref "C20") (pin "2") (pinfunction "2_2") (pintype "passive"))
      (node (ref "C21") (pin "2") (pinfunction "2_2") (pintype "passive"))
      (node (ref "C22") (pin "2") (pinfunction "2_2") (pintype "passive"))
      (node (ref "C23") (pin "2") (pinfunction "2_2") (pintype "passive"))
      (node (ref "C24") (pin "2") (pinfunction "2_2") (pintype "passive"))
      (node (ref "U12") (pin "14") (pinfunction "Vcc_14") (pintype "power_in"))
      (node (ref "U13") (pin "14") (pinfunction "Vcc_14") (pintype "power_in"))
      (node (ref "U14") (pin "14") (pinfunction "Vcc_14") (pintype "power_in"))
      (node (ref "U15") (pin "14") (pinfunction "Vcc_14") (pintype "power_in"))
      (node (ref "U16") (pin "14") (pinfunction "Vcc_14") (pintype "power_in"))
      (node (ref "U17") (pin "14") (pinfunction "Vcc_14") (pintype "power_in"))
    )
    (net (code "2") (name "/D1.1.E.1") (class "Default")
      (node (ref "D22") (pin "1") (pinfunction "A_1") (pintype "passive"))
    )
    (net (code "3") (name "/D1.1.E.2") (class "Default")
      (node (ref "D23") (pin "1") (pinfunction "A_1") (pintype "passive"))
    )
    (net (code "4") (name "/D1.1.F.1") (class "Default")
      (node (ref "D20") (pin "1") (pinfunction "A_1") (pintype "passive"))
    )
    (net (code "5") (name "/D1.1.F.2") (class "Default")
      (node (ref "D21") (pin "1") (pinfunction "A_1") (pintype "passive"))
    )
    (net (code "6") (name "/D1.2.E.1") (class "Default")
      (node (ref "D26") (pin "1") (pinfunction "A_1") (pintype "passive"))
    )
    (net (code "7") (name "/D1.2.E.2") (class "Default")
      (node (ref "D27") (pin "1") (pinfunction "A_1") (pintype "passive"))
    )
    (net (code "8") (name "/D1.2.F.1") (class "Default")
      (node (ref "D24") (pin "1") (pinfunction "A_1") (pintype "passive"))
    )
    (net (code "9") (name "/D1.2.F.2") (class "Default")
      (node (ref "D25") (pin "1") (pinfunction "A_1") (pintype "passive"))
    )
    (net (code "10") (name "/D1.3.E.1") (class "Default")
      (node (ref "D31") (pin "1") (pinfunction "A_1") (pintype "passive"))
    )
    (net (code "11") (name "/D1.3.E.2") (class "Default")
      (node (ref "D32") (pin "1") (pinfunction "A_1") (pintype "passive"))
    )
    (net (code "12") (name "/D1.3.E.3") (class "Default")
      (node (ref "D33") (pin "1") (pinfunction "A_1") (pintype "passive"))
    )
    (net (code "13") (name "/D1.3.F.1") (class "Default")
      (node (ref "D28") (pin "1") (pinfunction "A_1") (pintype "passive"))
    )
    (net (code "14") (name "/D1.3.F.2") (class "Default")
      (node (ref "D29") (pin "1") (pinfunction "A_1") (pintype "passive"))
    )
    (net (code "15") (name "/D1.3.F.3") (class "Default")
      (node (ref "D30") (pin "1") (pinfunction "A_1") (pintype "passive"))
    )
    (net (code "16") (name "/D1.AB.1") (class "Default")
      (node (ref "D34") (pin "1") (pinfunction "A_1") (pintype "passive"))
    )
    (net (code "17") (name "/D1.AB.2") (class "Default")
      (node (ref "D35") (pin "1") (pinfunction "A_1") (pintype "passive"))
    )
    (net (code "18") (name "/D1.AD.1") (class "Default")
      (node (ref "D36") (pin "1") (pinfunction "A_1") (pintype "passive"))
    )
    (net (code "19") (name "/D1.AD.2") (class "Default")
      (node (ref "D37") (pin "1") (pinfunction "A_1") (pintype "passive"))
    )
    (net (code "20") (name "/D2.1.E") (class "Default")
      (node (ref "D39") (pin "1") (pinfunction "A_1") (pintype "passive"))
    )
    (net (code "21") (name "/D2.1.F") (class "Default")
      (node (ref "D38") (pin "1") (pinfunction "A_1") (pintype "passive"))
    )
    (net (code "22") (name "/D2.2.E") (class "Default")
      (node (ref "D41") (pin "1") (pinfunction "A_1") (pintype "passive"))
    )
    (net (code "23") (name "/D2.2.F") (class "Default")
      (node (ref "D40") (pin "1") (pinfunction "A_1") (pintype "passive"))
    )
    (net (code "24") (name "/D2.3.E.1") (class "Default")
      (node (ref "D44") (pin "1") (pinfunction "A_1") (pintype "passive"))
    )
    (net (code "25") (name "/D2.3.E.2") (class "Default")
      (node (ref "D45") (pin "1") (pinfunction "A_1") (pintype "passive"))
    )
    (net (code "26") (name "/D2.3.F.1") (class "Default")
      (node (ref "D42") (pin "1") (pinfunction "A_1") (pintype "passive"))
    )
    (net (code "27") (name "/D2.3.F.2") (class "Default")
      (node (ref "D43") (pin "1") (pinfunction "A_1") (pintype "passive"))
    )
    (net (code "28") (name "/D2.AB") (class "Default")
      (node (ref "D46") (pin "1") (pinfunction "A_1") (pintype "passive"))
    )
    (net (code "29") (name "/D2.AD") (class "Default")
      (node (ref "D47") (pin "1") (pinfunction "A_1") (pintype "passive"))
    )
    (net (code "30") (name "/D3.1.E") (class "Default")
      (node (ref "D49") (pin "1") (pinfunction "A_1") (pintype "passive"))
    )
    (net (code "31") (name "/D3.1.F") (class "Default")
      (node (ref "D48") (pin "1") (pinfunction "A_1") (pintype "passive"))
    )
    (net (code "32") (name "/D3.2.E") (class "Default")
      (node (ref "D51") (pin "1") (pinfunction "A_1") (pintype "passive"))
    )
    (net (code "33") (name "/D3.2.F") (class "Default")
      (node (ref "D50") (pin "1") (pinfunction "A_1") (pintype "passive"))
    )
    (net (code "34") (name "/D3.3.E.1") (class "Default")
      (node (ref "D54") (pin "1") (pinfunction "A_1") (pintype "passive"))
    )
    (net (code "35") (name "/D3.3.E.2") (class "Default")
      (node (ref "D55") (pin "1") (pinfunction "A_1") (pintype "passive"))
    )
    (net (code "36") (name "/D3.3.F.1") (class "Default")
      (node (ref "D52") (pin "1") (pinfunction "A_1") (pintype "passive"))
    )
    (net (code "37") (name "/D3.3.F.2") (class "Default")
      (node (ref "D53") (pin "1") (pinfunction "A_1") (pintype "passive"))
    )
    (net (code "38") (name "/D4.1.E") (class "Default")
      (node (ref "D57") (pin "1") (pinfunction "A_1") (pintype "passive"))
    )
    (net (code "39") (name "/D4.1.F") (class "Default")
      (node (ref "D56") (pin "1") (pinfunction "A_1") (pintype "passive"))
    )
    (net (code "40") (name "/D4.2.E") (class "Default")
      (node (ref "D59") (pin "1") (pinfunction "A_1") (pintype "passive"))
    )
    (net (code "41") (name "/D4.2.F") (class "Default")
      (node (ref "D58") (pin "1") (pinfunction "A_1") (pintype "passive"))
    )
    (net (code "42") (name "/D4.3.E.1") (class "Default")
      (node (ref "D62") (pin "1") (pinfunction "A_1") (pintype "passive"))
    )
    (net (code "43") (name "/D4.3.E.2") (class "Default")
      (node (ref "D63") (pin "1") (pinfunction "A_1") (pintype "passive"))
    )
    (net (code "44") (name "/D4.3.F.1") (class "Default")
      (node (ref "D60") (pin "1") (pinfunction "A_1") (pintype "passive"))
    )
    (net (code "45") (name "/D4.3.F.2") (class "Default")
      (node (ref "D61") (pin "1") (pinfunction "A_1") (pintype "passive"))
    )
    (net (code "46") (name "/D4.AB") (class "Default")
      (node (ref "D64") (pin "1") (pinfunction "A_1") (pintype "passive"))
    )
    (net (code "47") (name "/D4.AD") (class "Default")
      (node (ref "D65") (pin "1") (pinfunction "A_1") (pintype "passive"))
    )
    (net (code "48") (name "/D5.1.E") (class "Default")
      (node (ref "D67") (pin "1") (pinfunction "A_1") (pintype "passive"))
    )
    (net (code "49") (name "/D5.1.F") (class "Default")
      (node (ref "D66") (pin "1") (pinfunction "A_1") (pintype "passive"))
    )
    (net (code "50") (name "/D5.2.E") (class "Default")
      (node (ref "D69") (pin "1") (pinfunction "A_1") (pintype "passive"))
    )
    (net (code "51") (name "/D5.2.F") (class "Default")
      (node (ref "D68") (pin "1") (pinfunction "A_1") (pintype "passive"))
    )
    (net (code "52") (name "/D5.3.E") (class "Default")
      (node (ref "D71") (pin "1") (pinfunction "A_1") (pintype "passive"))
    )
    (net (code "53") (name "/D5.3.F") (class "Default")
      (node (ref "D70") (pin "1") (pinfunction "A_1") (pintype "passive"))
    )
    (net (code "54") (name "/D5.AB") (class "Default")
      (node (ref "D72") (pin "1") (pinfunction "A_1") (pintype "passive"))
    )
    (net (code "55") (name "/D5.AD") (class "Default")
      (node (ref "D73") (pin "1") (pinfunction "A_1") (pintype "passive"))
    )
    (net (code "56") (name "/G.3.3.F.1") (class "Default")
      (node (ref "Q33") (pin "2") (pinfunction "G_2") (pintype "passive"))
      (node (ref "Q34") (pin "2") (pinfunction "G_2") (pintype "passive"))
      (node (ref "R42") (pin "2") (pinfunction "2_2") (pintype "passive"))
      (node (ref "R43") (pin "2") (pinfunction "2_2") (pintype "passive"))
      (node (ref "U15") (pin "2") (pinfunction "Y1_2") (pintype "power_in"))
    )
    (net (code "57") (name "/G.4.3.F.1") (class "Default")
      (node (ref "Q41") (pin "2") (pinfunction "G_2") (pintype "passive"))
      (node (ref "Q42") (pin "2") (pinfunction "G_2") (pintype "passive"))
      (node (ref "R50") (pin "2") (pinfunction "2_2") (pintype "passive"))
      (node (ref "R51") (pin "2") (pinfunction "2_2") (pintype "passive"))
      (node (ref "U16") (pin "2") (pinfunction "Y1_2") (pintype "power_in"))
    )
    (net (code "58") (name "/G1.1.E.1") (class "Default")
      (node (ref "Q3") (pin "2") (pinfunction "G_2") (pintype "passive"))
      (node (ref "Q4") (pin "2") (pinfunction "G_2") (pintype "passive"))
      (node (ref "R14") (pin "2") (pinfunction "2_2") (pintype "passive"))
      (node (ref "R15") (pin "2") (pinfunction "2_2") (pintype "passive"))
      (node (ref "U12") (pin "4") (pinfunction "Y2_4") (pintype "power_in"))
    )
    (net (code "59") (name "/G1.1.F.1") (class "Default")
      (node (ref "Q1") (pin "2") (pinfunction "G_2") (pintype "passive"))
      (node (ref "Q2") (pin "2") (pinfunction "G_2") (pintype "passive"))
      (node (ref "R66") (pin "2") (pinfunction "2_2") (pintype "passive"))
      (node (ref "R67") (pin "2") (pinfunction "2_2") (pintype "passive"))
      (node (ref "U12") (pin "2") (pinfunction "Y1_2") (pintype "power_in"))
    )
    (net (code "60") (name "/G1.2.E.1") (class "Default")
      (node (ref "Q7") (pin "2") (pinfunction "G_2") (pintype "passive"))
      (node (ref "Q8") (pin "2") (pinfunction "G_2") (pintype "passive"))
      (node (ref "R18") (pin "2") (pinfunction "2_2") (pintype "passive"))
      (node (ref "R19") (pin "2") (pinfunction "2_2") (pintype "passive"))
      (node (ref "U12") (pin "12") (pinfunction "Y6_12") (pintype "power_in"))
    )
    (net (code "61") (name "/G1.2.F.1") (class "Default")
      (node (ref "Q5") (pin "2") (pinfunction "G_2") (pintype "passive"))
      (node (ref "Q6") (pin "2") (pinfunction "G_2") (pintype "passive"))
      (node (ref "R16") (pin "2") (pinfunction "2_2") (pintype "passive"))
      (node (ref "R17") (pin "2") (pinfunction "2_2") (pintype "passive"))
      (node (ref "U12") (pin "6") (pinfunction "Y3_6") (pintype "power_in"))
    )
    (net (code "62") (name "/G1.3.E.1") (class "Default")
      (node (ref "Q12") (pin "2") (pinfunction "G_2") (pintype "passive"))
      (node (ref "Q13") (pin "2") (pinfunction "G_2") (pintype "passive"))
      (node (ref "Q14") (pin "2") (pinfunction "G_2") (pintype "passive"))
      (node (ref "R23") (pin "2") (pinfunction "2_2") (pintype "passive"))
      (node (ref "R24") (pin "2") (pinfunction "2_2") (pintype "passive"))
      (node (ref "R25") (pin "2") (pinfunction "2_2") (pintype "passive"))
      (node (ref "U12") (pin "8") (pinfunction "Y4_8") (pintype "power_in"))
    )
    (net (code "63") (name "/G1.3.F.1") (class "Default")
      (node (ref "Q10") (pin "2") (pinfunction "G_2") (pintype "passive"))
      (node (ref "Q11") (pin "2") (pinfunction "G_2") (pintype "passive"))
      (node (ref "Q9") (pin "2") (pinfunction "G_2") (pintype "passive"))
      (node (ref "R20") (pin "2") (pinfunction "2_2") (pintype "passive"))
      (node (ref "R21") (pin "2") (pinfunction "2_2") (pintype "passive"))
      (node (ref "R22") (pin "2") (pinfunction "2_2") (pintype "passive"))
      (node (ref "U12") (pin "10") (pinfunction "Y5_10") (pintype "power_in"))
    )
    (net (code "64") (name "/G1.AB.1") (class "Default")
      (node (ref "Q15") (pin "2") (pinfunction "G_2") (pintype "passive"))
      (node (ref "Q16") (pin "2") (pinfunction "G_2") (pintype "passive"))
      (node (ref "R26") (pin "2") (pinfunction "2_2") (pintype "passive"))
      (node (ref "R27") (pin "2") (pinfunction "2_2") (pintype "passive"))
      (node (ref "U13") (pin "2") (pinfunction "Y1_2") (pintype "power_in"))
    )
    (net (code "65") (name "/G1.AD.1") (class "Default")
      (node (ref "Q17") (pin "2") (pinfunction "G_2") (pintype "passive"))
      (node (ref "Q18") (pin "2") (pinfunction "G_2") (pintype "passive"))
      (node (ref "R28") (pin "2") (pinfunction "2_2") (pintype "passive"))
      (node (ref "R29") (pin "2") (pinfunction "2_2") (pintype "passive"))
      (node (ref "U13") (pin "4") (pinfunction "Y2_4") (pintype "power_in"))
    )
    (net (code "66") (name "/G2.1.AD") (class "Default")
      (node (ref "Q28") (pin "2") (pinfunction "G_2") (pintype "passive"))
      (node (ref "R39") (pin "2") (pinfunction "2_2") (pintype "passive"))
      (node (ref "U14") (pin "12") (pinfunction "Y6_12") (pintype "power_in"))
    )
    (net (code "67") (name "/G2.1.E") (class "Default")
      (node (ref "Q20") (pin "2") (pinfunction "G_2") (pintype "passive"))
      (node (ref "R31") (pin "2") (pinfunction "2_2") (pintype "passive"))
      (node (ref "U13") (pin "12") (pinfunction "Y6_12") (pintype "power_in"))
    )
    (net (code "68") (name "/G2.1.F") (class "Default")
      (node (ref "Q19") (pin "2") (pinfunction "G_2") (pintype "passive"))
      (node (ref "R30") (pin "2") (pinfunction "2_2") (pintype "passive"))
      (node (ref "U13") (pin "6") (pinfunction "Y3_6") (pintype "power_in"))
    )
    (net (code "69") (name "/G2.2.E") (class "Default")
      (node (ref "Q22") (pin "2") (pinfunction "G_2") (pintype "passive"))
      (node (ref "R33") (pin "2") (pinfunction "2_2") (pintype "passive"))
      (node (ref "U13") (pin "8") (pinfunction "Y4_8") (pintype "power_in"))
    )
    (net (code "70") (name "/G2.2.F") (class "Default")
      (node (ref "Q21") (pin "2") (pinfunction "G_2") (pintype "passive"))
      (node (ref "R32") (pin "2") (pinfunction "2_2") (pintype "passive"))
      (node (ref "U13") (pin "10") (pinfunction "Y5_10") (pintype "power_in"))
    )
    (net (code "71") (name "/G2.3.E.1") (class "Default")
      (node (ref "Q25") (pin "2") (pinfunction "G_2") (pintype "passive"))
      (node (ref "Q26") (pin "2") (pinfunction "G_2") (pintype "passive"))
      (node (ref "R36") (pin "2") (pinfunction "2_2") (pintype "passive"))
      (node (ref "R37") (pin "2") (pinfunction "2_2") (pintype "passive"))
      (node (ref "U14") (pin "4") (pinfunction "Y2_4") (pintype "power_in"))
    )
    (net (code "72") (name "/G2.3.F.1") (class "Default")
      (node (ref "Q23") (pin "2") (pinfunction "G_2") (pintype "passive"))
      (node (ref "Q24") (pin "2") (pinfunction "G_2") (pintype "passive"))
      (node (ref "R34") (pin "2") (pinfunction "2_2") (pintype "passive"))
      (node (ref "R35") (pin "2") (pinfunction "2_2") (pintype "passive"))
      (node (ref "U14") (pin "2") (pinfunction "Y1_2") (pintype "power_in"))
    )
    (net (code "73") (name "/G2.AB") (class "Default")
      (node (ref "Q27") (pin "2") (pinfunction "G_2") (pintype "passive"))
      (node (ref "R38") (pin "2") (pinfunction "2_2") (pintype "passive"))
      (node (ref "U14") (pin "6") (pinfunction "Y3_6") (pintype "power_in"))
    )
    (net (code "74") (name "/G3.1.E") (class "Default")
      (node (ref "Q30") (pin "2") (pinfunction "G_2") (pintype "passive"))
      (node (ref "R41") (pin "2") (pinfunction "2_2") (pintype "passive"))
      (node (ref "U14") (pin "8") (pinfunction "Y4_8") (pintype "power_in"))
    )
    (net (code "75") (name "/G3.1.F") (class "Default")
      (node (ref "Q29") (pin "2") (pinfunction "G_2") (pintype "passive"))
      (node (ref "R40") (pin "2") (pinfunction "2_2") (pintype "passive"))
      (node (ref "U14") (pin "10") (pinfunction "Y5_10") (pintype "power_in"))
    )
    (net (code "76") (name "/G3.2.E") (class "Default")
      (node (ref "Q32") (pin "2") (pinfunction "G_2") (pintype "passive"))
      (node (ref "R47") (pin "2") (pinfunction "2_2") (pintype "passive"))
      (node (ref "U15") (pin "12") (pinfunction "Y6_12") (pintype "power_in"))
    )
    (net (code "77") (name "/G3.2.F") (class "Default")
      (node (ref "Q31") (pin "2") (pinfunction "G_2") (pintype "passive"))
      (node (ref "R46") (pin "2") (pinfunction "2_2") (pintype "passive"))
      (node (ref "U15") (pin "6") (pinfunction "Y3_6") (pintype "power_in"))
    )
    (net (code "78") (name "/G3.3.E.1") (class "Default")
      (node (ref "Q35") (pin "2") (pinfunction "G_2") (pintype "passive"))
      (node (ref "Q36") (pin "2") (pinfunction "G_2") (pintype "passive"))
      (node (ref "R44") (pin "2") (pinfunction "2_2") (pintype "passive"))
      (node (ref "R45") (pin "2") (pinfunction "2_2") (pintype "passive"))
      (node (ref "U15") (pin "4") (pinfunction "Y2_4") (pintype "power_in"))
    )
    (net (code "79") (name "/G4.1.E") (class "Default")
      (node (ref "Q38") (pin "2") (pinfunction "G_2") (pintype "passive"))
      (node (ref "R49") (pin "2") (pinfunction "2_2") (pintype "passive"))
      (node (ref "U15") (pin "8") (pinfunction "Y4_8") (pintype "power_in"))
    )
    (net (code "80") (name "/G4.1.F") (class "Default")
      (node (ref "Q37") (pin "2") (pinfunction "G_2") (pintype "passive"))
      (node (ref "R48") (pin "2") (pinfunction "2_2") (pintype "passive"))
      (node (ref "U15") (pin "10") (pinfunction "Y5_10") (pintype "power_in"))
    )
    (net (code "81") (name "/G4.2.E") (class "Default")
      (node (ref "Q40") (pin "2") (pinfunction "G_2") (pintype "passive"))
      (node (ref "R55") (pin "2") (pinfunction "2_2") (pintype "passive"))
      (node (ref "U16") (pin "12") (pinfunction "Y6_12") (pintype "power_in"))
    )
    (net (code "82") (name "/G4.2.F") (class "Default")
      (node (ref "Q39") (pin "2") (pinfunction "G_2") (pintype "passive"))
      (node (ref "R54") (pin "2") (pinfunction "2_2") (pintype "passive"))
      (node (ref "U16") (pin "6") (pinfunction "Y3_6") (pintype "power_in"))
    )
    (net (code "83") (name "/G4.3.E.1") (class "Default")
      (node (ref "Q43") (pin "2") (pinfunction "G_2") (pintype "passive"))
      (node (ref "Q44") (pin "2") (pinfunction "G_2") (pintype "passive"))
      (node (ref "R52") (pin "2") (pinfunction "2_2") (pintype "passive"))
      (node (ref "R53") (pin "2") (pinfunction "2_2") (pintype "passive"))
      (node (ref "U16") (pin "4") (pinfunction "Y2_4") (pintype "power_in"))
    )
    (net (code "84") (name "/G4.AB") (class "Default")
      (node (ref "Q45") (pin "2") (pinfunction "G_2") (pintype "passive"))
      (node (ref "R56") (pin "2") (pinfunction "2_2") (pintype "passive"))
      (node (ref "U16") (pin "10") (pinfunction "Y5_10") (pintype "power_in"))
    )
    (net (code "85") (name "/G4.AD") (class "Default")
      (node (ref "Q46") (pin "2") (pinfunction "G_2") (pintype "passive"))
      (node (ref "R57") (pin "2") (pinfunction "2_2") (pintype "passive"))
      (node (ref "U16") (pin "8") (pinfunction "Y4_8") (pintype "power_in"))
    )
    (net (code "86") (name "/G5.1.E") (class "Default")
      (node (ref "Q48") (pin "2") (pinfunction "G_2") (pintype "passive"))
      (node (ref "R59") (pin "2") (pinfunction "2_2") (pintype "passive"))
      (node (ref "U17") (pin "4") (pinfunction "Y2_4") (pintype "power_in"))
    )
    (net (code "87") (name "/G5.1.F") (class "Default")
      (node (ref "Q47") (pin "2") (pinfunction "G_2") (pintype "passive"))
      (node (ref "R58") (pin "2") (pinfunction "2_2") (pintype "passive"))
      (node (ref "U17") (pin "2") (pinfunction "Y1_2") (pintype "power_in"))
    )
    (net (code "88") (name "/G5.2.E") (class "Default")
      (node (ref "Q50") (pin "2") (pinfunction "G_2") (pintype "passive"))
      (node (ref "R61") (pin "2") (pinfunction "2_2") (pintype "passive"))
      (node (ref "U17") (pin "12") (pinfunction "Y6_12") (pintype "power_in"))
    )
    (net (code "89") (name "/G5.2.F") (class "Default")
      (node (ref "Q49") (pin "2") (pinfunction "G_2") (pintype "passive"))
      (node (ref "R60") (pin "2") (pinfunction "2_2") (pintype "passive"))
      (node (ref "U17") (pin "6") (pinfunction "Y3_6") (pintype "power_in"))
    )
    (net (code "90") (name "/G5.3.E") (class "Default")
      (node (ref "Q52") (pin "2") (pinfunction "G_2") (pintype "passive"))
      (node (ref "R63") (pin "2") (pinfunction "2_2") (pintype "passive"))
      (node (ref "U17") (pin "8") (pinfunction "Y4_8") (pintype "power_in"))
    )
    (net (code "91") (name "/G5.3.F") (class "Default")
      (node (ref "Q51") (pin "2") (pinfunction "G_2") (pintype "passive"))
      (node (ref "R62") (pin "2") (pinfunction "2_2") (pintype "passive"))
      (node (ref "U17") (pin "10") (pinfunction "Y5_10") (pintype "power_in"))
    )
    (net (code "92") (name "/G5.AB") (class "Default")
      (node (ref "Q53") (pin "2") (pinfunction "G_2") (pintype "passive"))
      (node (ref "R64") (pin "2") (pinfunction "2_2") (pintype "passive"))
    )
    (net (code "93") (name "/G5.AD") (class "Default")
      (node (ref "Q54") (pin "2") (pinfunction "G_2") (pintype "passive"))
      (node (ref "R65") (pin "2") (pinfunction "2_2") (pintype "passive"))
    )
    (net (code "94") (name "/O1.1.E") (class "Default")
      (node (ref "U12") (pin "3") (pinfunction "A2_3") (pintype "power_in"))
    )
    (net (code "95") (name "/O1.1.F") (class "Default")
      (node (ref "U12") (pin "1") (pinfunction "A1_1") (pintype "power_in"))
    )
    (net (code "96") (name "/O1.2.E") (class "Default")
      (node (ref "U12") (pin "13") (pinfunction "A6_13") (pintype "power_in"))
    )
    (net (code "97") (name "/O1.2.F") (class "Default")
      (node (ref "U12") (pin "5") (pinfunction "A3_5") (pintype "power_in"))
    )
    (net (code "98") (name "/O1.3.E") (class "Default")
      (node (ref "U12") (pin "9") (pinfunction "A4_9") (pintype "power_in"))
    )
    (net (code "99") (name "/O1.3.F") (class "Default")
      (node (ref "U12") (pin "11") (pinfunction "A5_11") (pintype "power_in"))
    )
    (net (code "100") (name "/O1.AB") (class "Default")
      (node (ref "U13") (pin "1") (pinfunction "A1_1") (pintype "power_in"))
    )
    (net (code "101") (name "/O1.AD") (class "Default")
      (node (ref "U13") (pin "3") (pinfunction "A2_3") (pintype "power_in"))
    )
    (net (code "102") (name "/O2.1.E") (class "Default")
      (node (ref "U13") (pin "13") (pinfunction "A6_13") (pintype "power_in"))
    )
    (net (code "103") (name "/O2.1.F") (class "Default")
      (node (ref "U13") (pin "5") (pinfunction "A3_5") (pintype "power_in"))
    )
    (net (code "104") (name "/O2.2.E") (class "Default")
      (node (ref "U13") (pin "9") (pinfunction "A4_9") (pintype "power_in"))
    )
    (net (code "105") (name "/O2.2.F") (class "Default")
      (node (ref "U13") (pin "11") (pinfunction "A5_11") (pintype "power_in"))
    )
    (net (code "106") (name "/O2.3.E") (class "Default")
      (node (ref "U14") (pin "3") (pinfunction "A2_3") (pintype "power_in"))
    )
    (net (code "107") (name "/O2.3.F") (class "Default")
      (node (ref "U14") (pin "1") (pinfunction "A1_1") (pintype "power_in"))
    )
    (net (code "108") (name "/O2.AB") (class "Default")
      (node (ref "U14") (pin "5") (pinfunction "A3_5") (pintype "power_in"))
    )
    (net (code "109") (name "/O2.AD") (class "Default")
      (node (ref "U14") (pin "13") (pinfunction "A6_13") (pintype "power_in"))
    )
    (net (code "110") (name "/O3.1.E") (class "Default")
      (node (ref "U14") (pin "9") (pinfunction "A4_9") (pintype "power_in"))
    )
    (net (code "111") (name "/O3.1.F") (class "Default")
      (node (ref "U14") (pin "11") (pinfunction "A5_11") (pintype "power_in"))
    )
    (net (code "112") (name "/O3.2.E") (class "Default")
      (node (ref "U15") (pin "13") (pinfunction "A6_13") (pintype "power_in"))
    )
    (net (code "113") (name "/O3.2.F") (class "Default")
      (node (ref "U15") (pin "5") (pinfunction "A3_5") (pintype "power_in"))
    )
    (net (code "114") (name "/O3.3.E") (class "Default")
      (node (ref "U15") (pin "3") (pinfunction "A2_3") (pintype "power_in"))
    )
    (net (code "115") (name "/O3.3.F") (class "Default")
      (node (ref "U15") (pin "1") (pinfunction "A1_1") (pintype "power_in"))
    )
    (net (code "116") (name "/O4.1.E") (class "Default")
      (node (ref "U15") (pin "9") (pinfunction "A4_9") (pintype "power_in"))
    )
    (net (code "117") (name "/O4.1.F") (class "Default")
      (node (ref "U15") (pin "11") (pinfunction "A5_11") (pintype "power_in"))
    )
    (net (code "118") (name "/O4.2.E") (class "Default")
      (node (ref "U16") (pin "13") (pinfunction "A6_13") (pintype "power_in"))
    )
    (net (code "119") (name "/O4.2.F") (class "Default")
      (node (ref "U16") (pin "5") (pinfunction "A3_5") (pintype "power_in"))
    )
    (net (code "120") (name "/O4.3.E") (class "Default")
      (node (ref "U16") (pin "3") (pinfunction "A2_3") (pintype "power_in"))
    )
    (net (code "121") (name "/O4.3.F") (class "Default")
      (node (ref "U16") (pin "1") (pinfunction "A1_1") (pintype "power_in"))
    )
    (net (code "122") (name "/O4.AB") (class "Default")
      (node (ref "U16") (pin "11") (pinfunction "A5_11") (pintype "power_in"))
    )
    (net (code "123") (name "/O4.AD") (class "Default")
      (node (ref "U16") (pin "9") (pinfunction "A4_9") (pintype "power_in"))
    )
    (net (code "124") (name "/O5.1.E") (class "Default")
      (node (ref "U17") (pin "3") (pinfunction "A2_3") (pintype "power_in"))
    )
    (net (code "125") (name "/O5.1.F") (class "Default")
      (node (ref "U17") (pin "1") (pinfunction "A1_1") (pintype "power_in"))
    )
    (net (code "126") (name "/O5.2.E") (class "Default")
      (node (ref "U17") (pin "13") (pinfunction "A6_13") (pintype "power_in"))
    )
    (net (code "127") (name "/O5.2.F") (class "Default")
      (node (ref "U17") (pin "5") (pinfunction "A3_5") (pintype "power_in"))
    )
    (net (code "128") (name "/O5.3.E") (class "Default")
      (node (ref "U17") (pin "9") (pinfunction "A4_9") (pintype "power_in"))
    )
    (net (code "129") (name "/O5.3.F") (class "Default")
      (node (ref "U17") (pin "11") (pinfunction "A5_11") (pintype "power_in"))
    )
    (net (code "130") (name "GND") (class "Default")
      (node (ref "C19") (pin "1") (pinfunction "1_1") (pintype "passive"))
      (node (ref "C20") (pin "1") (pinfunction "1_1") (pintype "passive"))
      (node (ref "C21") (pin "1") (pinfunction "1_1") (pintype "passive"))
      (node (ref "C22") (pin "1") (pinfunction "1_1") (pintype "passive"))
      (node (ref "C23") (pin "1") (pinfunction "1_1") (pintype "passive"))
      (node (ref "C24") (pin "1") (pinfunction "1_1") (pintype "passive"))
      (node (ref "Q1") (pin "3") (pinfunction "S_3") (pintype "passive"))
      (node (ref "Q10") (pin "3") (pinfunction "S_3") (pintype "passive"))
      (node (ref "Q11") (pin "3") (pinfunction "S_3") (pintype "passive"))
      (node (ref "Q12") (pin "3") (pinfunction "S_3") (pintype "passive"))
      (node (ref "Q13") (pin "3") (pinfunction "S_3") (pintype "passive"))
      (node (ref "Q14") (pin "3") (pinfunction "S_3") (pintype "passive"))
      (node (ref "Q15") (pin "3") (pinfunction "S_3") (pintype "passive"))
      (node (ref "Q16") (pin "3") (pinfunction "S_3") (pintype "passive"))
      (node (ref "Q17") (pin "3") (pinfunction "S_3") (pintype "passive"))
      (node (ref "Q18") (pin "3") (pinfunction "S_3") (pintype "passive"))
      (node (ref "Q19") (pin "3") (pinfunction "S_3") (pintype "passive"))
      (node (ref "Q2") (pin "3") (pinfunction "S_3") (pintype "passive"))
      (node (ref "Q20") (pin "3") (pinfunction "S_3") (pintype "passive"))
      (node (ref "Q21") (pin "3") (pinfunction "S_3") (pintype "passive"))
      (node (ref "Q22") (pin "3") (pinfunction "S_3") (pintype "passive"))
      (node (ref "Q23") (pin "3") (pinfunction "S_3") (pintype "passive"))
      (node (ref "Q24") (pin "3") (pinfunction "S_3") (pintype "passive"))
      (node (ref "Q25") (pin "3") (pinfunction "S_3") (pintype "passive"))
      (node (ref "Q26") (pin "3") (pinfunction "S_3") (pintype "passive"))
      (node (ref "Q27") (pin "3") (pinfunction "S_3") (pintype "passive"))
      (node (ref "Q28") (pin "3") (pinfunction "S_3") (pintype "passive"))
      (node (ref "Q29") (pin "3") (pinfunction "S_3") (pintype "passive"))
      (node (ref "Q3") (pin "3") (pinfunction "S_3") (pintype "passive"))
      (node (ref "Q30") (pin "3") (pinfunction "S_3") (pintype "passive"))
      (node (ref "Q31") (pin "3") (pinfunction "S_3") (pintype "passive"))
      (node (ref "Q32") (pin "3") (pinfunction "S_3") (pintype "passive"))
      (node (ref "Q33") (pin "3") (pinfunction "S_3") (pintype "passive"))
      (node (ref "Q34") (pin "3") (pinfunction "S_3") (pintype "passive"))
      (node (ref "Q35") (pin "3") (pinfunction "S_3") (pintype "passive"))
      (node (ref "Q36") (pin "3") (pinfunction "S_3") (pintype "passive"))
      (node (ref "Q37") (pin "3") (pinfunction "S_3") (pintype "passive"))
      (node (ref "Q38") (pin "3") (pinfunction "S_3") (pintype "passive"))
      (node (ref "Q39") (pin "3") (pinfunction "S_3") (pintype "passive"))
      (node (ref "Q4") (pin "3") (pinfunction "S_3") (pintype "passive"))
      (node (ref "Q40") (pin "3") (pinfunction "S_3") (pintype "passive"))
      (node (ref "Q41") (pin "3") (pinfunction "S_3") (pintype "passive"))
      (node (ref "Q42") (pin "3") (pinfunction "S_3") (pintype "passive"))
      (node (ref "Q43") (pin "3") (pinfunction "S_3") (pintype "passive"))
      (node (ref "Q44") (pin "3") (pinfunction "S_3") (pintype "passive"))
      (node (ref "Q45") (pin "3") (pinfunction "S_3") (pintype "passive"))
      (node (ref "Q46") (pin "3") (pinfunction "S_3") (pintype "passive"))
      (node (ref "Q47") (pin "3") (pinfunction "S_3") (pintype "passive"))
      (node (ref "Q48") (pin "3") (pinfunction "S_3") (pintype "passive"))
      (node (ref "Q49") (pin "3") (pinfunction "S_3") (pintype "passive"))
      (node (ref "Q5") (pin "3") (pinfunction "S_3") (pintype "passive"))
      (node (ref "Q50") (pin "3") (pinfunction "S_3") (pintype "passive"))
      (node (ref "Q51") (pin "3") (pinfunction "S_3") (pintype "passive"))
      (node (ref "Q52") (pin "3") (pinfunction "S_3") (pintype "passive"))
      (node (ref "Q53") (pin "3") (pinfunction "S_3") (pintype "passive"))
      (node (ref "Q54") (pin "3") (pinfunction "S_3") (pintype "passive"))
      (node (ref "Q6") (pin "3") (pinfunction "S_3") (pintype "passive"))
      (node (ref "Q7") (pin "3") (pinfunction "S_3") (pintype "passive"))
      (node (ref "Q8") (pin "3") (pinfunction "S_3") (pintype "passive"))
      (node (ref "Q9") (pin "3") (pinfunction "S_3") (pintype "passive"))
      (node (ref "R14") (pin "1") (pinfunction "1_1") (pintype "passive"))
      (node (ref "R15") (pin "1") (pinfunction "1_1") (pintype "passive"))
      (node (ref "R16") (pin "1") (pinfunction "1_1") (pintype "passive"))
      (node (ref "R17") (pin "1") (pinfunction "1_1") (pintype "passive"))
      (node (ref "R18") (pin "1") (pinfunction "1_1") (pintype "passive"))
      (node (ref "R19") (pin "1") (pinfunction "1_1") (pintype "passive"))
      (node (ref "R20") (pin "1") (pinfunction "1_1") (pintype "passive"))
      (node (ref "R21") (pin "1") (pinfunction "1_1") (pintype "passive"))
      (node (ref "R22") (pin "1") (pinfunction "1_1") (pintype "passive"))
      (node (ref "R23") (pin "1") (pinfunction "1_1") (pintype "passive"))
      (node (ref "R24") (pin "1") (pinfunction "1_1") (pintype "passive"))
      (node (ref "R25") (pin "1") (pinfunction "1_1") (pintype "passive"))
      (node (ref "R26") (pin "1") (pinfunction "1_1") (pintype "passive"))
      (node (ref "R27") (pin "1") (pinfunction "1_1") (pintype "passive"))
      (node (ref "R28") (pin "1") (pinfunction "1_1") (pintype "passive"))
      (node (ref "R29") (pin "1") (pinfunction "1_1") (pintype "passive"))
      (node (ref "R30") (pin "1") (pinfunction "1_1") (pintype "passive"))
      (node (ref "R31") (pin "1") (pinfunction "1_1") (pintype "passive"))
      (node (ref "R32") (pin "1") (pinfunction "1_1") (pintype "passive"))
      (node (ref "R33") (pin "1") (pinfunction "1_1") (pintype "passive"))
      (node (ref "R34") (pin "1") (pinfunction "1_1") (pintype "passive"))
      (node (ref "R35") (pin "1") (pinfunction "1_1") (pintype "passive"))
      (node (ref "R36") (pin "1") (pinfunction "1_1") (pintype "passive"))
      (node (ref "R37") (pin "1") (pinfunction "1_1") (pintype "passive"))
      (node (ref "R38") (pin "1") (pinfunction "1_1") (pintype "passive"))
      (node (ref "R39") (pin "1") (pinfunction "1_1") (pintype "passive"))
      (node (ref "R40") (pin "1") (pinfunction "1_1") (pintype "passive"))
      (node (ref "R41") (pin "1") (pinfunction "1_1") (pintype "passive"))
      (node (ref "R42") (pin "1") (pinfunction "1_1") (pintype "passive"))
      (node (ref "R43") (pin "1") (pinfunction "1_1") (pintype "passive"))
      (node (ref "R44") (pin "1") (pinfunction "1_1") (pintype "passive"))
      (node (ref "R45") (pin "1") (pinfunction "1_1") (pintype "passive"))
      (node (ref "R46") (pin "1") (pinfunction "1_1") (pintype "passive"))
      (node (ref "R47") (pin "1") (pinfunction "1_1") (pintype "passive"))
      (node (ref "R48") (pin "1") (pinfunction "1_1") (pintype "passive"))
      (node (ref "R49") (pin "1") (pinfunction "1_1") (pintype "passive"))
      (node (ref "R50") (pin "1") (pinfunction "1_1") (pintype "passive"))
      (node (ref "R51") (pin "1") (pinfunction "1_1") (pintype "passive"))
      (node (ref "R52") (pin "1") (pinfunction "1_1") (pintype "passive"))
      (node (ref "R53") (pin "1") (pinfunction "1_1") (pintype "passive"))
      (node (ref "R54") (pin "1") (pinfunction "1_1") (pintype "passive"))
      (node (ref "R55") (pin "1") (pinfunction "1_1") (pintype "passive"))
      (node (ref "R56") (pin "1") (pinfunction "1_1") (pintype "passive"))
      (node (ref "R57") (pin "1") (pinfunction "1_1") (pintype "passive"))
      (node (ref "R58") (pin "1") (pinfunction "1_1") (pintype "passive"))
      (node (ref "R59") (pin "1") (pinfunction "1_1") (pintype "passive"))
      (node (ref "R60") (pin "1") (pinfunction "1_1") (pintype "passive"))
      (node (ref "R61") (pin "1") (pinfunction "1_1") (pintype "passive"))
      (node (ref "R62") (pin "1") (pinfunction "1_1") (pintype "passive"))
      (node (ref "R63") (pin "1") (pinfunction "1_1") (pintype "passive"))
      (node (ref "R64") (pin "1") (pinfunction "1_1") (pintype "passive"))
      (node (ref "R65") (pin "1") (pinfunction "1_1") (pintype "passive"))
      (node (ref "R66") (pin "1") (pinfunction "1_1") (pintype "passive"))
      (node (ref "R67") (pin "1") (pinfunction "1_1") (pintype "passive"))
      (node (ref "U12") (pin "7") (pinfunction "GND_7") (pintype "power_in"))
      (node (ref "U13") (pin "7") (pinfunction "GND_7") (pintype "power_in"))
      (node (ref "U14") (pin "7") (pinfunction "GND_7") (pintype "power_in"))
      (node (ref "U15") (pin "7") (pinfunction "GND_7") (pintype "power_in"))
      (node (ref "U16") (pin "7") (pinfunction "GND_7") (pintype "power_in"))
      (node (ref "U17") (pin "7") (pinfunction "GND_7") (pintype "power_in"))
    )
    (net (code "131") (name "Net-(D20-K)") (class "Default")
      (node (ref "D20") (pin "2") (pinfunction "K_2") (pintype "passive"))
      (node (ref "Q1") (pin "1") (pinfunction "D_1") (pintype "passive"))
    )
    (net (code "132") (name "Net-(D21-K)") (class "Default")
      (node (ref "D21") (pin "2") (pinfunction "K_2") (pintype "passive"))
      (node (ref "Q2") (pin "1") (pinfunction "D_1") (pintype "passive"))
    )
    (net (code "133") (name "Net-(D22-K)") (class "Default")
      (node (ref "D22") (pin "2") (pinfunction "K_2") (pintype "passive"))
      (node (ref "Q3") (pin "1") (pinfunction "D_1") (pintype "passive"))
    )
    (net (code "134") (name "Net-(D23-K)") (class "Default")
      (node (ref "D23") (pin "2") (pinfunction "K_2") (pintype "passive"))
      (node (ref "Q4") (pin "1") (pinfunction "D_1") (pintype "passive"))
    )
    (net (code "135") (name "Net-(D24-K)") (class "Default")
      (node (ref "D24") (pin "2") (pinfunction "K_2") (pintype "passive"))
      (node (ref "Q5") (pin "1") (pinfunction "D_1") (pintype "passive"))
    )
    (net (code "136") (name "Net-(D25-K)") (class "Default")
      (node (ref "D25") (pin "2") (pinfunction "K_2") (pintype "passive"))
      (node (ref "Q6") (pin "1") (pinfunction "D_1") (pintype "passive"))
    )
    (net (code "137") (name "Net-(D26-K)") (class "Default")
      (node (ref "D26") (pin "2") (pinfunction "K_2") (pintype "passive"))
      (node (ref "Q7") (pin "1") (pinfunction "D_1") (pintype "passive"))
    )
    (net (code "138") (name "Net-(D27-K)") (class "Default")
      (node (ref "D27") (pin "2") (pinfunction "K_2") (pintype "passive"))
      (node (ref "Q8") (pin "1") (pinfunction "D_1") (pintype "passive"))
    )
    (net (code "139") (name "Net-(D28-K)") (class "Default")
      (node (ref "D28") (pin "2") (pinfunction "K_2") (pintype "passive"))
      (node (ref "Q9") (pin "1") (pinfunction "D_1") (pintype "passive"))
    )
    (net (code "140") (name "Net-(D29-K)") (class "Default")
      (node (ref "D29") (pin "2") (pinfunction "K_2") (pintype "passive"))
      (node (ref "Q10") (pin "1") (pinfunction "D_1") (pintype "passive"))
    )
    (net (code "141") (name "Net-(D30-K)") (class "Default")
      (node (ref "D30") (pin "2") (pinfunction "K_2") (pintype "passive"))
      (node (ref "Q11") (pin "1") (pinfunction "D_1") (pintype "passive"))
    )
    (net (code "142") (name "Net-(D31-K)") (class "Default")
      (node (ref "D31") (pin "2") (pinfunction "K_2") (pintype "passive"))
      (node (ref "Q12") (pin "1") (pinfunction "D_1") (pintype "passive"))
    )
    (net (code "143") (name "Net-(D32-K)") (class "Default")
      (node (ref "D32") (pin "2") (pinfunction "K_2") (pintype "passive"))
      (node (ref "Q13") (pin "1") (pinfunction "D_1") (pintype "passive"))
    )
    (net (code "144") (name "Net-(D33-K)") (class "Default")
      (node (ref "D33") (pin "2") (pinfunction "K_2") (pintype "passive"))
      (node (ref "Q14") (pin "1") (pinfunction "D_1") (pintype "passive"))
    )
    (net (code "145") (name "Net-(D34-K)") (class "Default")
      (node (ref "D34") (pin "2") (pinfunction "K_2") (pintype "passive"))
      (node (ref "Q15") (pin "1") (pinfunction "D_1") (pintype "passive"))
    )
    (net (code "146") (name "Net-(D35-K)") (class "Default")
      (node (ref "D35") (pin "2") (pinfunction "K_2") (pintype "passive"))
      (node (ref "Q16") (pin "1") (pinfunction "D_1") (pintype "passive"))
    )
    (net (code "147") (name "Net-(D36-K)") (class "Default")
      (node (ref "D36") (pin "2") (pinfunction "K_2") (pintype "passive"))
      (node (ref "Q17") (pin "1") (pinfunction "D_1") (pintype "passive"))
    )
    (net (code "148") (name "Net-(D37-K)") (class "Default")
      (node (ref "D37") (pin "2") (pinfunction "K_2") (pintype "passive"))
      (node (ref "Q18") (pin "1") (pinfunction "D_1") (pintype "passive"))
    )
    (net (code "149") (name "Net-(D38-K)") (class "Default")
      (node (ref "D38") (pin "2") (pinfunction "K_2") (pintype "passive"))
      (node (ref "Q19") (pin "1") (pinfunction "D_1") (pintype "passive"))
    )
    (net (code "150") (name "Net-(D39-K)") (class "Default")
      (node (ref "D39") (pin "2") (pinfunction "K_2") (pintype "passive"))
      (node (ref "Q20") (pin "1") (pinfunction "D_1") (pintype "passive"))
    )
    (net (code "151") (name "Net-(D40-K)") (class "Default")
      (node (ref "D40") (pin "2") (pinfunction "K_2") (pintype "passive"))
      (node (ref "Q21") (pin "1") (pinfunction "D_1") (pintype "passive"))
    )
    (net (code "152") (name "Net-(D41-K)") (class "Default")
      (node (ref "D41") (pin "2") (pinfunction "K_2") (pintype "passive"))
      (node (ref "Q22") (pin "1") (pinfunction "D_1") (pintype "passive"))
    )
    (net (code "153") (name "Net-(D42-K)") (class "Default")
      (node (ref "D42") (pin "2") (pinfunction "K_2") (pintype "passive"))
      (node (ref "Q23") (pin "1") (pinfunction "D_1") (pintype "passive"))
    )
    (net (code "154") (name "Net-(D43-K)") (class "Default")
      (node (ref "D43") (pin "2") (pinfunction "K_2") (pintype "passive"))
      (node (ref "Q24") (pin "1") (pinfunction "D_1") (pintype "passive"))
    )
    (net (code "155") (name "Net-(D44-K)") (class "Default")
      (node (ref "D44") (pin "2") (pinfunction "K_2") (pintype "passive"))
      (node (ref "Q25") (pin "1") (pinfunction "D_1") (pintype "passive"))
    )
    (net (code "156") (name "Net-(D45-K)") (class "Default")
      (node (ref "D45") (pin "2") (pinfunction "K_2") (pintype "passive"))
      (node (ref "Q26") (pin "1") (pinfunction "D_1") (pintype "passive"))
    )
    (net (code "157") (name "Net-(D46-K)") (class "Default")
      (node (ref "D46") (pin "2") (pinfunction "K_2") (pintype "passive"))
      (node (ref "Q27") (pin "1") (pinfunction "D_1") (pintype "passive"))
    )
    (net (code "158") (name "Net-(D47-K)") (class "Default")
      (node (ref "D47") (pin "2") (pinfunction "K_2") (pintype "passive"))
      (node (ref "Q28") (pin "1") (pinfunction "D_1") (pintype "passive"))
    )
    (net (code "159") (name "Net-(D48-K)") (class "Default")
      (node (ref "D48") (pin "2") (pinfunction "K_2") (pintype "passive"))
      (node (ref "Q29") (pin "1") (pinfunction "D_1") (pintype "passive"))
    )
    (net (code "160") (name "Net-(D49-K)") (class "Default")
      (node (ref "D49") (pin "2") (pinfunction "K_2") (pintype "passive"))
      (node (ref "Q30") (pin "1") (pinfunction "D_1") (pintype "passive"))
    )
    (net (code "161") (name "Net-(D50-K)") (class "Default")
      (node (ref "D50") (pin "2") (pinfunction "K_2") (pintype "passive"))
      (node (ref "Q31") (pin "1") (pinfunction "D_1") (pintype "passive"))
    )
    (net (code "162") (name "Net-(D51-K)") (class "Default")
      (node (ref "D51") (pin "2") (pinfunction "K_2") (pintype "passive"))
      (node (ref "Q32") (pin "1") (pinfunction "D_1") (pintype "passive"))
    )
    (net (code "163") (name "Net-(D52-K)") (class "Default")
      (node (ref "D52") (pin "2") (pinfunction "K_2") (pintype "passive"))
      (node (ref "Q33") (pin "1") (pinfunction "D_1") (pintype "passive"))
    )
    (net (code "164") (name "Net-(D53-K)") (class "Default")
      (node (ref "D53") (pin "2") (pinfunction "K_2") (pintype "passive"))
      (node (ref "Q34") (pin "1") (pinfunction "D_1") (pintype "passive"))
    )
    (net (code "165") (name "Net-(D54-K)") (class "Default")
      (node (ref "D54") (pin "2") (pinfunction "K_2") (pintype "passive"))
      (node (ref "Q35") (pin "1") (pinfunction "D_1") (pintype "passive"))
    )
    (net (code "166") (name "Net-(D55-K)") (class "Default")
      (node (ref "D55") (pin "2") (pinfunction "K_2") (pintype "passive"))
      (node (ref "Q36") (pin "1") (pinfunction "D_1") (pintype "passive"))
    )
    (net (code "167") (name "Net-(D56-K)") (class "Default")
      (node (ref "D56") (pin "2") (pinfunction "K_2") (pintype "passive"))
      (node (ref "Q37") (pin "1") (pinfunction "D_1") (pintype "passive"))
    )
    (net (code "168") (name "Net-(D57-K)") (class "Default")
      (node (ref "D57") (pin "2") (pinfunction "K_2") (pintype "passive"))
      (node (ref "Q38") (pin "1") (pinfunction "D_1") (pintype "passive"))
    )
    (net (code "169") (name "Net-(D58-K)") (class "Default")
      (node (ref "D58") (pin "2") (pinfunction "K_2") (pintype "passive"))
      (node (ref "Q39") (pin "1") (pinfunction "D_1") (pintype "passive"))
    )
    (net (code "170") (name "Net-(D59-K)") (class "Default")
      (node (ref "D59") (pin "2") (pinfunction "K_2") (pintype "passive"))
      (node (ref "Q40") (pin "1") (pinfunction "D_1") (pintype "passive"))
    )
    (net (code "171") (name "Net-(D60-K)") (class "Default")
      (node (ref "D60") (pin "2") (pinfunction "K_2") (pintype "passive"))
      (node (ref "Q41") (pin "1") (pinfunction "D_1") (pintype "passive"))
    )
    (net (code "172") (name "Net-(D61-K)") (class "Default")
      (node (ref "D61") (pin "2") (pinfunction "K_2") (pintype "passive"))
      (node (ref "Q42") (pin "1") (pinfunction "D_1") (pintype "passive"))
    )
    (net (code "173") (name "Net-(D62-K)") (class "Default")
      (node (ref "D62") (pin "2") (pinfunction "K_2") (pintype "passive"))
      (node (ref "Q43") (pin "1") (pinfunction "D_1") (pintype "passive"))
    )
    (net (code "174") (name "Net-(D63-K)") (class "Default")
      (node (ref "D63") (pin "2") (pinfunction "K_2") (pintype "passive"))
      (node (ref "Q44") (pin "1") (pinfunction "D_1") (pintype "passive"))
    )
    (net (code "175") (name "Net-(D64-K)") (class "Default")
      (node (ref "D64") (pin "2") (pinfunction "K_2") (pintype "passive"))
      (node (ref "Q45") (pin "1") (pinfunction "D_1") (pintype "passive"))
    )
    (net (code "176") (name "Net-(D65-K)") (class "Default")
      (node (ref "D65") (pin "2") (pinfunction "K_2") (pintype "passive"))
      (node (ref "Q46") (pin "1") (pinfunction "D_1") (pintype "passive"))
    )
    (net (code "177") (name "Net-(D66-K)") (class "Default")
      (node (ref "D66") (pin "2") (pinfunction "K_2") (pintype "passive"))
      (node (ref "Q47") (pin "1") (pinfunction "D_1") (pintype "passive"))
    )
    (net (code "178") (name "Net-(D67-K)") (class "Default")
      (node (ref "D67") (pin "2") (pinfunction "K_2") (pintype "passive"))
      (node (ref "Q48") (pin "1") (pinfunction "D_1") (pintype "passive"))
    )
    (net (code "179") (name "Net-(D68-K)") (class "Default")
      (node (ref "D68") (pin "2") (pinfunction "K_2") (pintype "passive"))
      (node (ref "Q49") (pin "1") (pinfunction "D_1") (pintype "passive"))
    )
    (net (code "180") (name "Net-(D69-K)") (class "Default")
      (node (ref "D69") (pin "2") (pinfunction "K_2") (pintype "passive"))
      (node (ref "Q50") (pin "1") (pinfunction "D_1") (pintype "passive"))
    )
    (net (code "181") (name "Net-(D70-K)") (class "Default")
      (node (ref "D70") (pin "2") (pinfunction "K_2") (pintype "passive"))
      (node (ref "Q51") (pin "1") (pinfunction "D_1") (pintype "passive"))
    )
    (net (code "182") (name "Net-(D71-K)") (class "Default")
      (node (ref "D71") (pin "2") (pinfunction "K_2") (pintype "passive"))
      (node (ref "Q52") (pin "1") (pinfunction "D_1") (pintype "passive"))
    )
    (net (code "183") (name "Net-(D72-K)") (class "Default")
      (node (ref "D72") (pin "2") (pinfunction "K_2") (pintype "passive"))
      (node (ref "Q53") (pin "1") (pinfunction "D_1") (pintype "passive"))
    )
    (net (code "184") (name "Net-(D73-K)") (class "Default")
      (node (ref "D73") (pin "2") (pinfunction "K_2") (pintype "passive"))
      (node (ref "Q54") (pin "1") (pinfunction "D_1") (pintype "passive"))
    )
  )
)
